# mmu6100cp.net
KiCad netlist of a schematic drawn in EAGLE
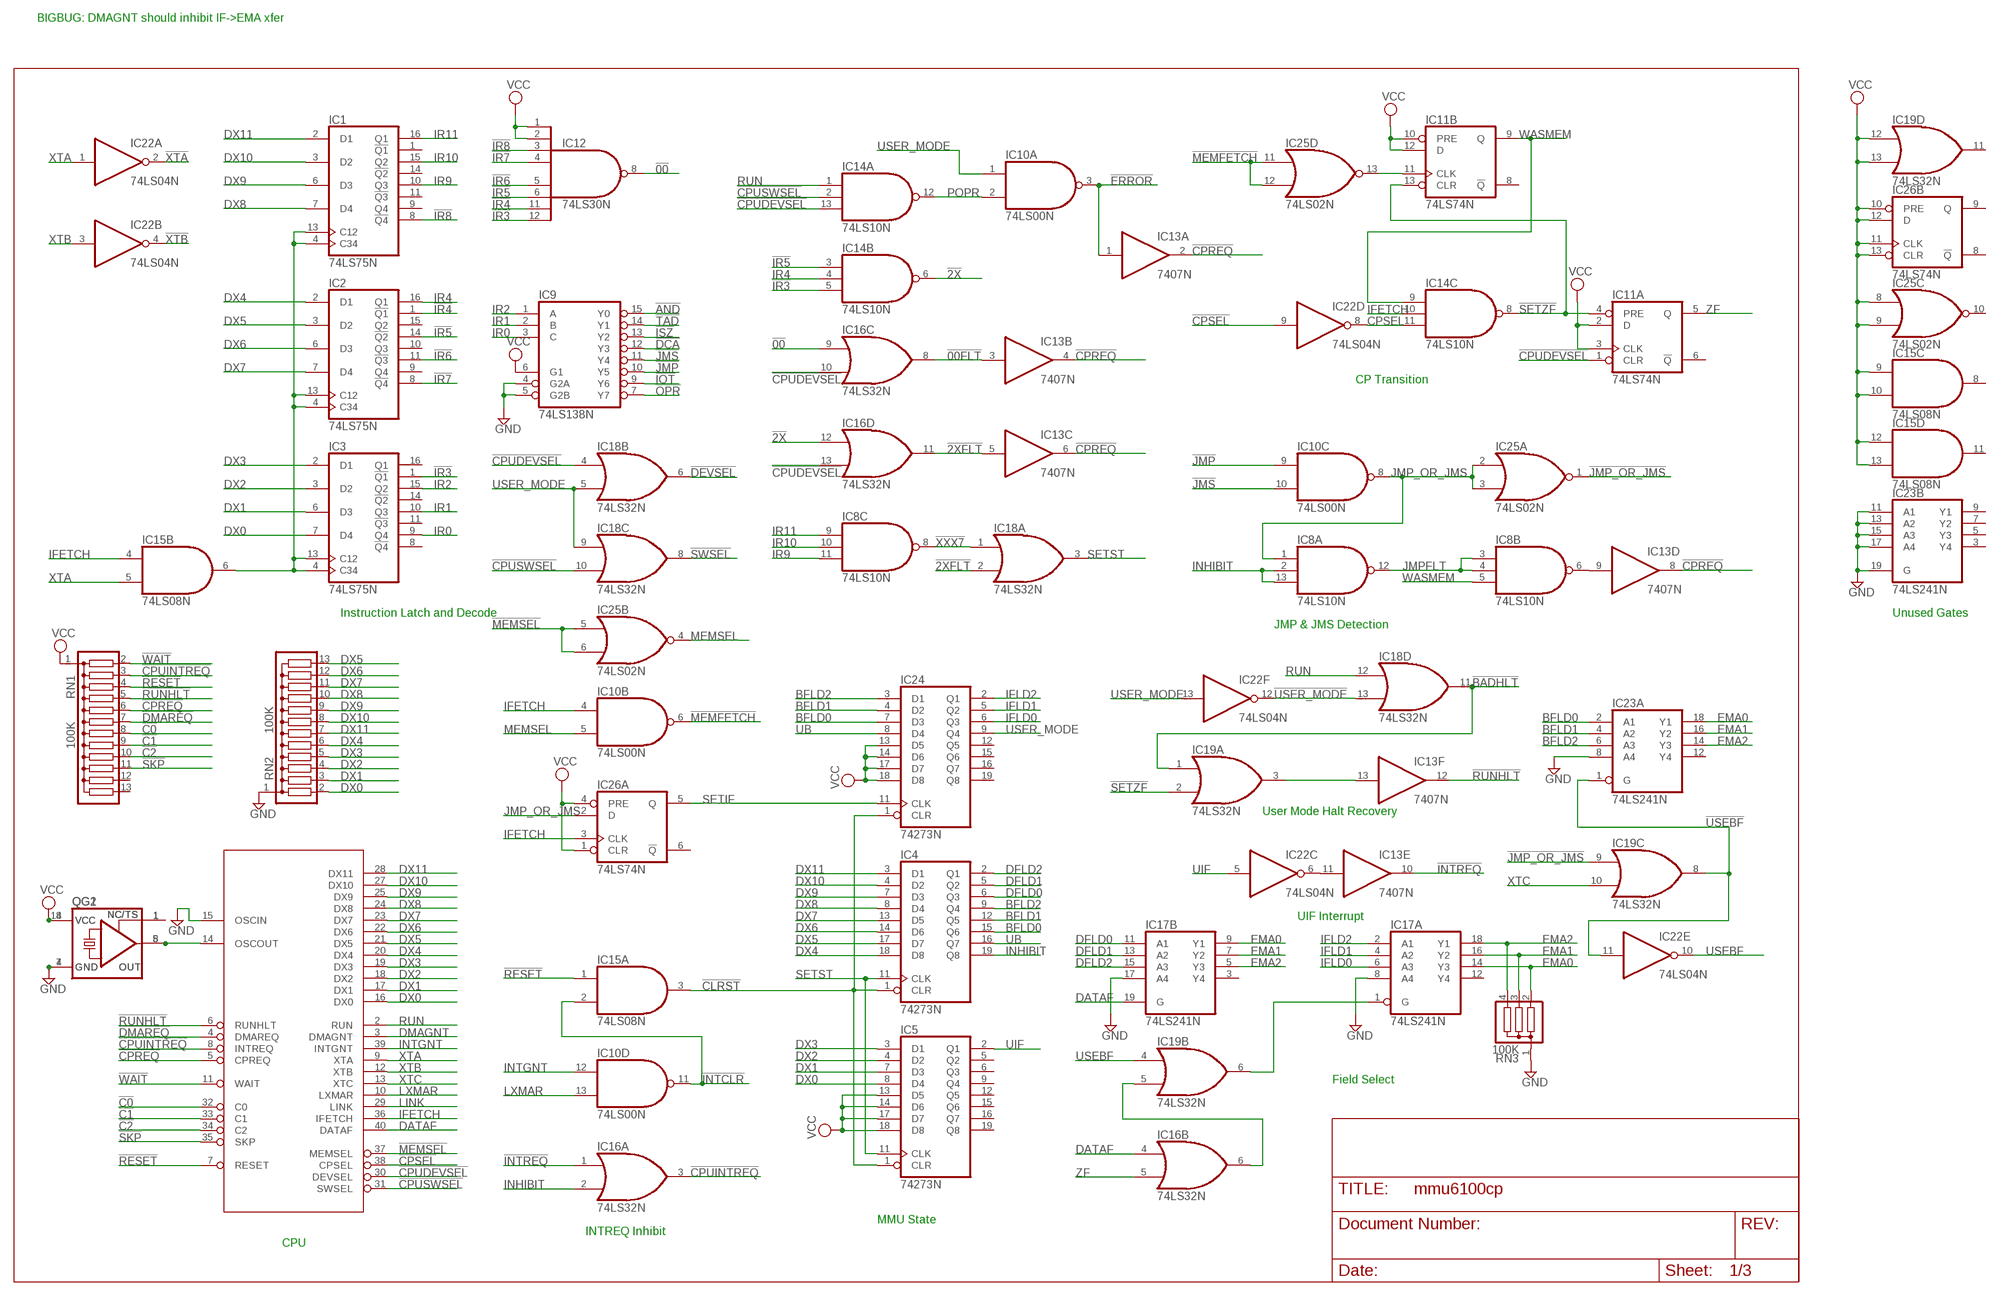
[diagram p0: schematic, sheet 1]
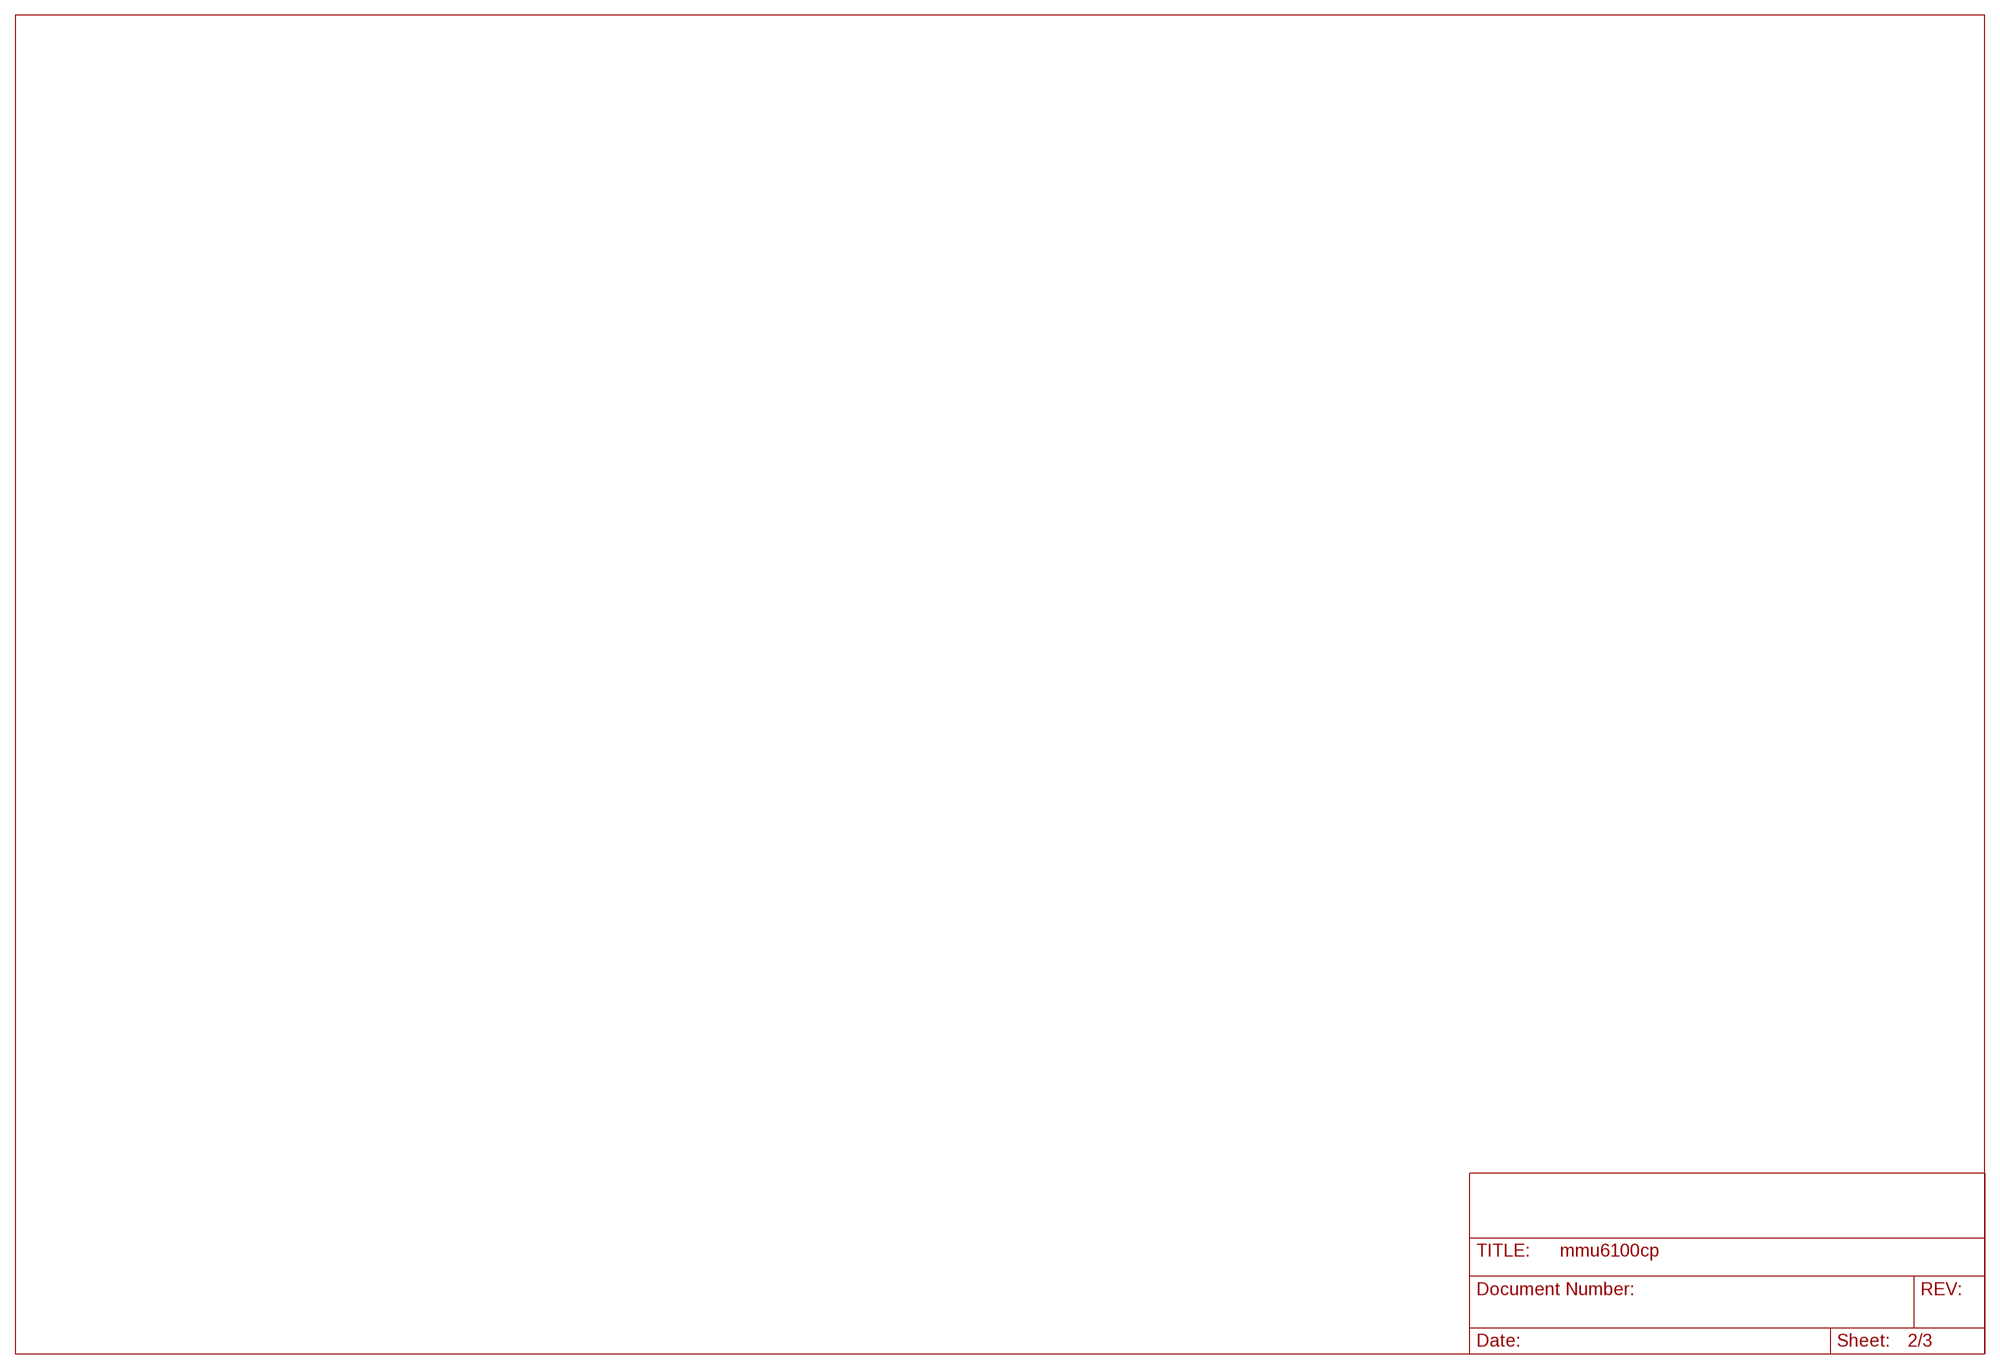
[diagram p1: schematic, sheet 2]
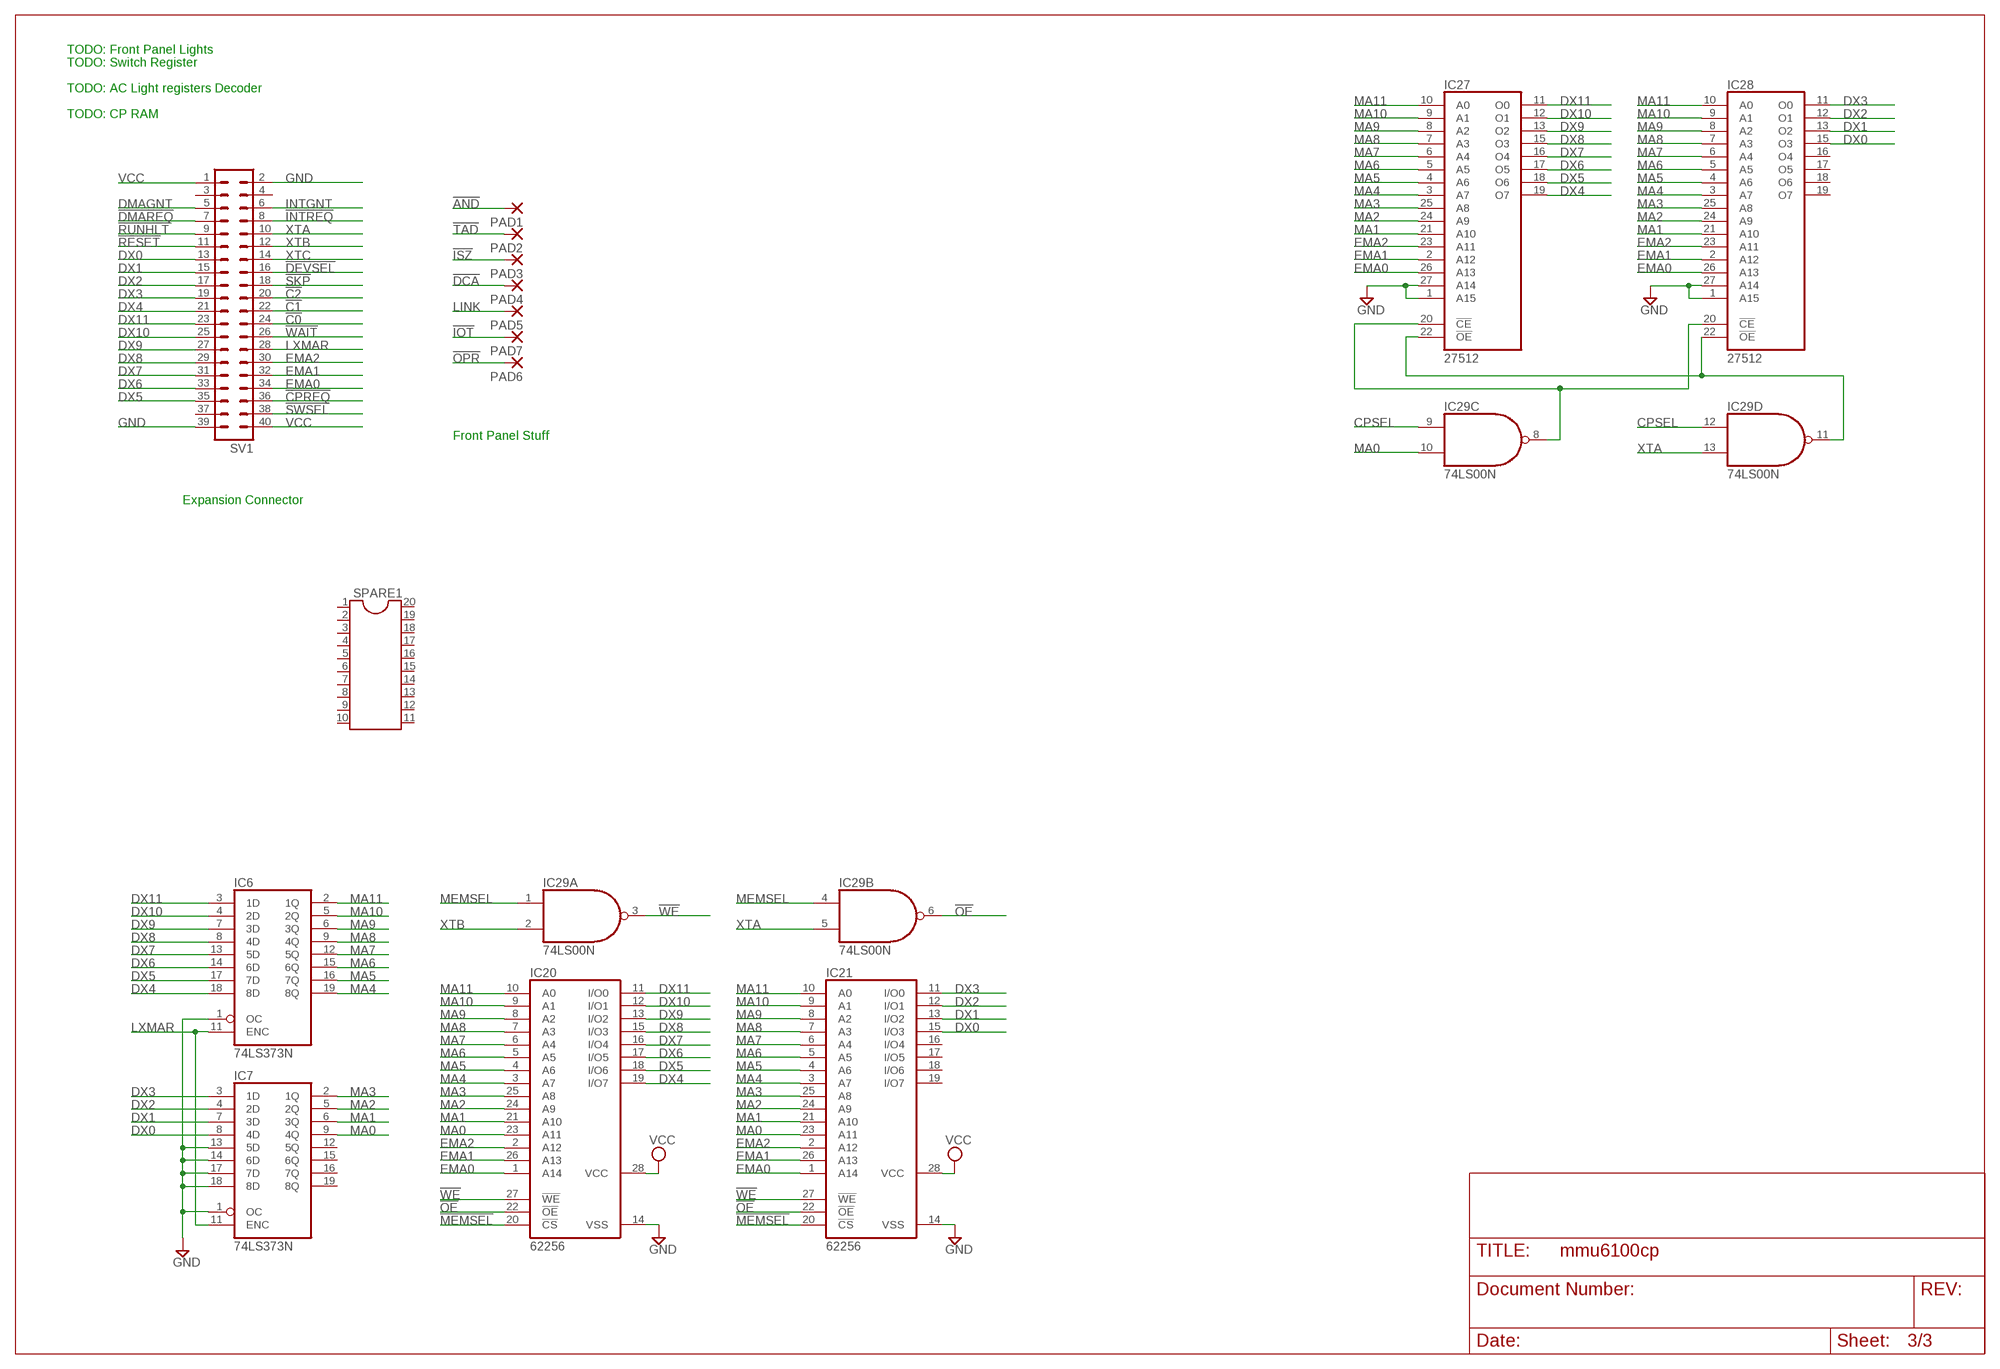
[diagram p2: schematic, sheet 3]

(export (version "E")
  (design (tool "Eeschema 10.0.6"))
  (components
    (comp (ref "IC6")
      (value "74LS373N")
      (footprint "eagle-import:DIL20")
      (libsource (lib "eagle-import") (part "74373NLS"))
    )
    (comp (ref "IC7")
      (value "74LS373N")
      (footprint "eagle-import:DIL20")
      (libsource (lib "eagle-import") (part "74373NLS"))
    )
    (comp (ref "IC20")
      (value "62256")
      (footprint "eagle-import:DIL28-6")
      (libsource (lib "eagle-import") (part "62256P"))
    )
    (comp (ref "IC21")
      (value "62256")
      (footprint "eagle-import:DIL28-6")
      (libsource (lib "eagle-import") (part "62256P"))
    )
    (comp (ref "IC27")
      (value "27512")
      (footprint "eagle-import:DIL28")
      (libsource (lib "eagle-import") (part "27512"))
    )
    (comp (ref "IC28")
      (value "27512")
      (footprint "eagle-import:DIL28")
      (libsource (lib "eagle-import") (part "27512"))
    )
    (comp (ref "IC29")
      (value "74LS00N")
      (footprint "eagle-import:DIL14")
      (libsource (lib "eagle-import") (part "7400NLS"))
    )
    (comp (ref "PAD1")
      (value "2,15/1,0")
      (footprint "eagle-import:2,15_1,0")
      (libsource (lib "eagle-import") (part "2,15/1,0"))
    )
    (comp (ref "PAD2")
      (value "2,15/1,0")
      (footprint "eagle-import:2,15_1,0")
      (libsource (lib "eagle-import") (part "2,15/1,0"))
    )
    (comp (ref "PAD3")
      (value "2,15/1,0")
      (footprint "eagle-import:2,15_1,0")
      (libsource (lib "eagle-import") (part "2,15/1,0"))
    )
    (comp (ref "PAD4")
      (value "2,15/1,0")
      (footprint "eagle-import:2,15_1,0")
      (libsource (lib "eagle-import") (part "2,15/1,0"))
    )
    (comp (ref "PAD5")
      (value "2,15/1,0")
      (footprint "eagle-import:2,15_1,0")
      (libsource (lib "eagle-import") (part "2,15/1,0"))
    )
    (comp (ref "PAD6")
      (value "2,15/1,0")
      (footprint "eagle-import:2,15_1,0")
      (libsource (lib "eagle-import") (part "2,15/1,0"))
    )
    (comp (ref "PAD7")
      (value "2,15/1,0")
      (footprint "eagle-import:2,15_1,0")
      (libsource (lib "eagle-import") (part "2,15/1,0"))
    )
    (comp (ref "SPARE1")
      (value "DIL20")
      (footprint "eagle-import:DIL20")
      (libsource (lib "eagle-import") (part "DIL20"))
    )
    (comp (ref "SV1")
      (value "MA20-2")
      (footprint "eagle-import:MA20-2")
      (libsource (lib "eagle-import") (part "MA20-2"))
    )
    (comp (ref "CPU")
      (value "IM6100")
      (footprint "eagle-import:DIL40")
      (libsource (lib "eagle-import") (part "IM6100"))
    )
    (comp (ref "IC1")
      (value "74LS75N")
      (footprint "eagle-import:DIL16")
      (libsource (lib "eagle-import") (part "7475NLS"))
    )
    (comp (ref "IC2")
      (value "74LS75N")
      (footprint "eagle-import:DIL16")
      (libsource (lib "eagle-import") (part "7475NLS"))
    )
    (comp (ref "IC3")
      (value "74LS75N")
      (footprint "eagle-import:DIL16")
      (libsource (lib "eagle-import") (part "7475NLS"))
    )
    (comp (ref "IC4")
      (value "74273N")
      (footprint "eagle-import:DIL20")
      (libsource (lib "eagle-import") (part "74273N"))
    )
    (comp (ref "IC5")
      (value "74273N")
      (footprint "eagle-import:DIL20")
      (libsource (lib "eagle-import") (part "74273N"))
    )
    (comp (ref "IC8")
      (value "74LS10N")
      (footprint "eagle-import:DIL14")
      (libsource (lib "eagle-import") (part "7410NLS"))
    )
    (comp (ref "IC9")
      (value "74LS138N")
      (footprint "eagle-import:DIL16")
      (libsource (lib "eagle-import") (part "74138NLS"))
    )
    (comp (ref "IC10")
      (value "74LS00N")
      (footprint "eagle-import:DIL14")
      (libsource (lib "eagle-import") (part "7400NLS"))
    )
    (comp (ref "IC11")
      (value "74LS74N")
      (footprint "eagle-import:DIL14")
      (libsource (lib "eagle-import") (part "7474NLS"))
    )
    (comp (ref "IC12")
      (value "74LS30N")
      (footprint "eagle-import:DIL14")
      (libsource (lib "eagle-import") (part "7430NLS"))
    )
    (comp (ref "IC13")
      (value "7407N")
      (footprint "eagle-import:DIL14")
      (libsource (lib "eagle-import") (part "7407N"))
    )
    (comp (ref "IC14")
      (value "74LS10N")
      (footprint "eagle-import:DIL14")
      (libsource (lib "eagle-import") (part "7410NLS"))
    )
    (comp (ref "IC15")
      (value "74LS08N")
      (footprint "eagle-import:DIL14")
      (libsource (lib "eagle-import") (part "7408NLS"))
    )
    (comp (ref "IC16")
      (value "74LS32N")
      (footprint "eagle-import:DIL14")
      (libsource (lib "eagle-import") (part "7432NLS"))
    )
    (comp (ref "IC17")
      (value "74LS241N")
      (footprint "eagle-import:DIL20")
      (libsource (lib "eagle-import") (part "74241NLS"))
    )
    (comp (ref "IC18")
      (value "74LS32N")
      (footprint "eagle-import:DIL14")
      (libsource (lib "eagle-import") (part "7432NLS"))
    )
    (comp (ref "IC19")
      (value "74LS32N")
      (footprint "eagle-import:DIL14")
      (libsource (lib "eagle-import") (part "7432NLS"))
    )
    (comp (ref "IC22")
      (value "74LS04N")
      (footprint "eagle-import:DIL14")
      (libsource (lib "eagle-import") (part "7404NLS"))
    )
    (comp (ref "IC23")
      (value "74LS241N")
      (footprint "eagle-import:DIL20")
      (libsource (lib "eagle-import") (part "74241NLS"))
    )
    (comp (ref "IC24")
      (value "74273N")
      (footprint "eagle-import:DIL20")
      (libsource (lib "eagle-import") (part "74273N"))
    )
    (comp (ref "IC25")
      (value "74LS02N")
      (footprint "eagle-import:DIL14")
      (libsource (lib "eagle-import") (part "7402NLS"))
    )
    (comp (ref "IC26")
      (value "74LS74N")
      (footprint "eagle-import:DIL14")
      (libsource (lib "eagle-import") (part "7474NLS"))
    )
    (comp (ref "QG1")
      (value "XO-8")
      (footprint "eagle-import:DIL08S")
      (libsource (lib "eagle-import") (part "XO-8"))
    )
    (comp (ref "QG2")
      (value "XO-14")
      (footprint "eagle-import:DIL14S")
      (libsource (lib "eagle-import") (part "XO-14"))
    )
    (comp (ref "RN1")
      (value "100K")
      (footprint "eagle-import:SIL13")
      (libsource (lib "eagle-import") (part "G12R"))
    )
    (comp (ref "RN2")
      (value "100K")
      (footprint "eagle-import:SIL13")
      (libsource (lib "eagle-import") (part "G12R"))
    )
    (comp (ref "RN3")
      (value "100K")
      (footprint "eagle-import:SIL4")
      (libsource (lib "eagle-import") (part "G03R"))
    )
  )
  (nets
    (net (code "1") (name "BFLD0") (class "Default")
      (node (ref "IC23") (pin "2") (pinfunction "A1_2") (pintype "input"))
      (node (ref "IC24") (pin "7") (pinfunction "D3_7") (pintype "input"))
      (node (ref "IC4") (pin "15") (pinfunction "Q6_15") (pintype "output"))
    )
    (net (code "2") (name "BFLD1") (class "Default")
      (node (ref "IC23") (pin "4") (pinfunction "A2_4") (pintype "input"))
      (node (ref "IC24") (pin "4") (pinfunction "D2_4") (pintype "input"))
      (node (ref "IC4") (pin "12") (pinfunction "Q5_12") (pintype "output"))
    )
    (net (code "3") (name "BFLD2") (class "Default")
      (node (ref "IC23") (pin "6") (pinfunction "A3_6") (pintype "input"))
      (node (ref "IC24") (pin "3") (pinfunction "D1_3") (pintype "input"))
      (node (ref "IC4") (pin "9") (pinfunction "Q4_9") (pintype "output"))
    )
    (net (code "4") (name "CPSEL") (class "Default")
      (node (ref "IC14") (pin "11") (pinfunction "I2_11") (pintype "input"))
      (node (ref "IC22") (pin "8") (pinfunction "O_8") (pintype "output"))
      (node (ref "IC29") (pin "12") (pinfunction "I0_12") (pintype "input"))
      (node (ref "IC29") (pin "9") (pinfunction "I0_9") (pintype "input"))
    )
    (net (code "5") (name "DATAF") (class "Default")
      (node (ref "CPU") (pin "40") (pinfunction "DATAF_40") (pintype "output"))
      (node (ref "IC16") (pin "4") (pinfunction "I0_4") (pintype "input"))
      (node (ref "IC17") (pin "19") (pinfunction "G_19") (pintype "input"))
    )
    (net (code "6") (name "DFLD0") (class "Default")
      (node (ref "IC17") (pin "11") (pinfunction "A1_11") (pintype "input"))
      (node (ref "IC4") (pin "6") (pinfunction "Q3_6") (pintype "output"))
    )
    (net (code "7") (name "DFLD1") (class "Default")
      (node (ref "IC17") (pin "13") (pinfunction "A2_13") (pintype "input"))
      (node (ref "IC4") (pin "5") (pinfunction "Q2_5") (pintype "output"))
    )
    (net (code "8") (name "DFLD2") (class "Default")
      (node (ref "IC17") (pin "15") (pinfunction "A3_15") (pintype "input"))
      (node (ref "IC4") (pin "2") (pinfunction "Q1_2") (pintype "output"))
    )
    (net (code "9") (name "DMAGNT") (class "Default")
      (node (ref "CPU") (pin "3") (pinfunction "DMAGNT_3") (pintype "output"))
      (node (ref "SV1") (pin "5") (pinfunction "5_5") (pintype "passive"))
    )
    (net (code "10") (name "DX0") (class "Default")
      (node (ref "CPU") (pin "16") (pinfunction "DX0_16") (pintype "bidirectional"))
      (node (ref "IC21") (pin "15") (pinfunction "I/O3_15") (pintype "bidirectional"))
      (node (ref "IC28") (pin "15") (pinfunction "O3_15") (pintype "tri_state"))
      (node (ref "IC3") (pin "7") (pinfunction "D4_7") (pintype "input"))
      (node (ref "IC5") (pin "8") (pinfunction "D4_8") (pintype "input"))
      (node (ref "IC7") (pin "8") (pinfunction "4D_8") (pintype "input"))
      (node (ref "RN2") (pin "2") (pinfunction "2_2") (pintype "passive"))
      (node (ref "SV1") (pin "13") (pinfunction "13_13") (pintype "passive"))
    )
    (net (code "11") (name "DX1") (class "Default")
      (node (ref "CPU") (pin "17") (pinfunction "DX1_17") (pintype "bidirectional"))
      (node (ref "IC21") (pin "13") (pinfunction "I/O2_13") (pintype "bidirectional"))
      (node (ref "IC28") (pin "13") (pinfunction "O2_13") (pintype "tri_state"))
      (node (ref "IC3") (pin "6") (pinfunction "D3_6") (pintype "input"))
      (node (ref "IC5") (pin "7") (pinfunction "D3_7") (pintype "input"))
      (node (ref "IC7") (pin "7") (pinfunction "3D_7") (pintype "input"))
      (node (ref "RN2") (pin "3") (pinfunction "3_3") (pintype "passive"))
      (node (ref "SV1") (pin "15") (pinfunction "15_15") (pintype "passive"))
    )
    (net (code "12") (name "DX2") (class "Default")
      (node (ref "CPU") (pin "18") (pinfunction "DX2_18") (pintype "bidirectional"))
      (node (ref "IC21") (pin "12") (pinfunction "I/O1_12") (pintype "bidirectional"))
      (node (ref "IC28") (pin "12") (pinfunction "O1_12") (pintype "tri_state"))
      (node (ref "IC3") (pin "3") (pinfunction "D2_3") (pintype "input"))
      (node (ref "IC5") (pin "4") (pinfunction "D2_4") (pintype "input"))
      (node (ref "IC7") (pin "4") (pinfunction "2D_4") (pintype "input"))
      (node (ref "RN2") (pin "4") (pinfunction "4_4") (pintype "passive"))
      (node (ref "SV1") (pin "17") (pinfunction "17_17") (pintype "passive"))
    )
    (net (code "13") (name "DX3") (class "Default")
      (node (ref "CPU") (pin "19") (pinfunction "DX3_19") (pintype "bidirectional"))
      (node (ref "IC21") (pin "11") (pinfunction "I/O0_11") (pintype "bidirectional"))
      (node (ref "IC28") (pin "11") (pinfunction "O0_11") (pintype "tri_state"))
      (node (ref "IC3") (pin "2") (pinfunction "D1_2") (pintype "input"))
      (node (ref "IC5") (pin "3") (pinfunction "D1_3") (pintype "input"))
      (node (ref "IC7") (pin "3") (pinfunction "1D_3") (pintype "input"))
      (node (ref "RN2") (pin "5") (pinfunction "5_5") (pintype "passive"))
      (node (ref "SV1") (pin "19") (pinfunction "19_19") (pintype "passive"))
    )
    (net (code "14") (name "DX4") (class "Default")
      (node (ref "CPU") (pin "20") (pinfunction "DX4_20") (pintype "bidirectional"))
      (node (ref "IC2") (pin "2") (pinfunction "D1_2") (pintype "input"))
      (node (ref "IC20") (pin "19") (pinfunction "I/O7_19") (pintype "bidirectional"))
      (node (ref "IC27") (pin "19") (pinfunction "O7_19") (pintype "tri_state"))
      (node (ref "IC4") (pin "18") (pinfunction "D8_18") (pintype "input"))
      (node (ref "IC6") (pin "18") (pinfunction "8D_18") (pintype "input"))
      (node (ref "RN2") (pin "6") (pinfunction "6_6") (pintype "passive"))
      (node (ref "SV1") (pin "21") (pinfunction "21_21") (pintype "passive"))
    )
    (net (code "15") (name "DX5") (class "Default")
      (node (ref "CPU") (pin "21") (pinfunction "DX5_21") (pintype "bidirectional"))
      (node (ref "IC2") (pin "3") (pinfunction "D2_3") (pintype "input"))
      (node (ref "IC20") (pin "18") (pinfunction "I/O6_18") (pintype "bidirectional"))
      (node (ref "IC27") (pin "18") (pinfunction "O6_18") (pintype "tri_state"))
      (node (ref "IC4") (pin "17") (pinfunction "D7_17") (pintype "input"))
      (node (ref "IC6") (pin "17") (pinfunction "7D_17") (pintype "input"))
      (node (ref "RN2") (pin "13") (pinfunction "13_13") (pintype "passive"))
      (node (ref "SV1") (pin "35") (pinfunction "35_35") (pintype "passive"))
    )
    (net (code "16") (name "DX6") (class "Default")
      (node (ref "CPU") (pin "22") (pinfunction "DX6_22") (pintype "bidirectional"))
      (node (ref "IC2") (pin "6") (pinfunction "D3_6") (pintype "input"))
      (node (ref "IC20") (pin "17") (pinfunction "I/O5_17") (pintype "bidirectional"))
      (node (ref "IC27") (pin "17") (pinfunction "O5_17") (pintype "tri_state"))
      (node (ref "IC4") (pin "14") (pinfunction "D6_14") (pintype "input"))
      (node (ref "IC6") (pin "14") (pinfunction "6D_14") (pintype "input"))
      (node (ref "RN2") (pin "12") (pinfunction "12_12") (pintype "passive"))
      (node (ref "SV1") (pin "33") (pinfunction "33_33") (pintype "passive"))
    )
    (net (code "17") (name "DX7") (class "Default")
      (node (ref "CPU") (pin "23") (pinfunction "DX7_23") (pintype "bidirectional"))
      (node (ref "IC2") (pin "7") (pinfunction "D4_7") (pintype "input"))
      (node (ref "IC20") (pin "16") (pinfunction "I/O4_16") (pintype "bidirectional"))
      (node (ref "IC27") (pin "16") (pinfunction "O4_16") (pintype "tri_state"))
      (node (ref "IC4") (pin "13") (pinfunction "D5_13") (pintype "input"))
      (node (ref "IC6") (pin "13") (pinfunction "5D_13") (pintype "input"))
      (node (ref "RN2") (pin "11") (pinfunction "11_11") (pintype "passive"))
      (node (ref "SV1") (pin "31") (pinfunction "31_31") (pintype "passive"))
    )
    (net (code "18") (name "DX8") (class "Default")
      (node (ref "CPU") (pin "24") (pinfunction "DX8_24") (pintype "bidirectional"))
      (node (ref "IC1") (pin "7") (pinfunction "D4_7") (pintype "input"))
      (node (ref "IC20") (pin "15") (pinfunction "I/O3_15") (pintype "bidirectional"))
      (node (ref "IC27") (pin "15") (pinfunction "O3_15") (pintype "tri_state"))
      (node (ref "IC4") (pin "8") (pinfunction "D4_8") (pintype "input"))
      (node (ref "IC6") (pin "8") (pinfunction "4D_8") (pintype "input"))
      (node (ref "RN2") (pin "10") (pinfunction "10_10") (pintype "passive"))
      (node (ref "SV1") (pin "29") (pinfunction "29_29") (pintype "passive"))
    )
    (net (code "19") (name "DX9") (class "Default")
      (node (ref "CPU") (pin "25") (pinfunction "DX9_25") (pintype "bidirectional"))
      (node (ref "IC1") (pin "6") (pinfunction "D3_6") (pintype "input"))
      (node (ref "IC20") (pin "13") (pinfunction "I/O2_13") (pintype "bidirectional"))
      (node (ref "IC27") (pin "13") (pinfunction "O2_13") (pintype "tri_state"))
      (node (ref "IC4") (pin "7") (pinfunction "D3_7") (pintype "input"))
      (node (ref "IC6") (pin "7") (pinfunction "3D_7") (pintype "input"))
      (node (ref "RN2") (pin "9") (pinfunction "9_9") (pintype "passive"))
      (node (ref "SV1") (pin "27") (pinfunction "27_27") (pintype "passive"))
    )
    (net (code "20") (name "DX10") (class "Default")
      (node (ref "CPU") (pin "27") (pinfunction "DX10_27") (pintype "bidirectional"))
      (node (ref "IC1") (pin "3") (pinfunction "D2_3") (pintype "input"))
      (node (ref "IC20") (pin "12") (pinfunction "I/O1_12") (pintype "bidirectional"))
      (node (ref "IC27") (pin "12") (pinfunction "O1_12") (pintype "tri_state"))
      (node (ref "IC4") (pin "4") (pinfunction "D2_4") (pintype "input"))
      (node (ref "IC6") (pin "4") (pinfunction "2D_4") (pintype "input"))
      (node (ref "RN2") (pin "8") (pinfunction "8_8") (pintype "passive"))
      (node (ref "SV1") (pin "25") (pinfunction "25_25") (pintype "passive"))
    )
    (net (code "21") (name "DX11") (class "Default")
      (node (ref "CPU") (pin "28") (pinfunction "DX11_28") (pintype "bidirectional"))
      (node (ref "IC1") (pin "2") (pinfunction "D1_2") (pintype "input"))
      (node (ref "IC20") (pin "11") (pinfunction "I/O0_11") (pintype "bidirectional"))
      (node (ref "IC27") (pin "11") (pinfunction "O0_11") (pintype "tri_state"))
      (node (ref "IC4") (pin "3") (pinfunction "D1_3") (pintype "input"))
      (node (ref "IC6") (pin "3") (pinfunction "1D_3") (pintype "input"))
      (node (ref "RN2") (pin "7") (pinfunction "7_7") (pintype "passive"))
      (node (ref "SV1") (pin "23") (pinfunction "23_23") (pintype "passive"))
    )
    (net (code "22") (name "EMA0") (class "Default")
      (node (ref "IC17") (pin "14") (pinfunction "Y3_14") (pintype "tri_state"))
      (node (ref "IC17") (pin "9") (pinfunction "Y1_9") (pintype "tri_state"))
      (node (ref "IC20") (pin "1") (pinfunction "A14_1") (pintype "input"))
      (node (ref "IC21") (pin "1") (pinfunction "A14_1") (pintype "input"))
      (node (ref "IC23") (pin "18") (pinfunction "Y1_18") (pintype "tri_state"))
      (node (ref "IC27") (pin "26") (pinfunction "A13_26") (pintype "input"))
      (node (ref "IC28") (pin "26") (pinfunction "A13_26") (pintype "input"))
      (node (ref "RN3") (pin "2") (pinfunction "2_2") (pintype "passive"))
      (node (ref "SV1") (pin "34") (pinfunction "34_34") (pintype "passive"))
    )
    (net (code "23") (name "EMA1") (class "Default")
      (node (ref "IC17") (pin "16") (pinfunction "Y2_16") (pintype "tri_state"))
      (node (ref "IC17") (pin "7") (pinfunction "Y2_7") (pintype "tri_state"))
      (node (ref "IC20") (pin "26") (pinfunction "A13_26") (pintype "input"))
      (node (ref "IC21") (pin "26") (pinfunction "A13_26") (pintype "input"))
      (node (ref "IC23") (pin "16") (pinfunction "Y2_16") (pintype "tri_state"))
      (node (ref "IC27") (pin "2") (pinfunction "A12_2") (pintype "input"))
      (node (ref "IC28") (pin "2") (pinfunction "A12_2") (pintype "input"))
      (node (ref "RN3") (pin "3") (pinfunction "3_3") (pintype "passive"))
      (node (ref "SV1") (pin "32") (pinfunction "32_32") (pintype "passive"))
    )
    (net (code "24") (name "EMA2") (class "Default")
      (node (ref "IC17") (pin "18") (pinfunction "Y1_18") (pintype "tri_state"))
      (node (ref "IC17") (pin "5") (pinfunction "Y3_5") (pintype "tri_state"))
      (node (ref "IC20") (pin "2") (pinfunction "A12_2") (pintype "input"))
      (node (ref "IC21") (pin "2") (pinfunction "A12_2") (pintype "input"))
      (node (ref "IC23") (pin "14") (pinfunction "Y3_14") (pintype "tri_state"))
      (node (ref "IC27") (pin "23") (pinfunction "A11_23") (pintype "input"))
      (node (ref "IC28") (pin "23") (pinfunction "A11_23") (pintype "input"))
      (node (ref "RN3") (pin "4") (pinfunction "4_4") (pintype "passive"))
      (node (ref "SV1") (pin "30") (pinfunction "30_30") (pintype "passive"))
    )
    (net (code "25") (name "GND") (class "Default")
      (node (ref "CPU") (pin "15") (pinfunction "OSCIN_15") (pintype "input"))
      (node (ref "IC17") (pin "17") (pinfunction "A4_17") (pintype "input"))
      (node (ref "IC17") (pin "8") (pinfunction "A4_8") (pintype "input"))
      (node (ref "IC20") (pin "14") (pinfunction "VSS_14") (pintype "power_in"))
      (node (ref "IC21") (pin "14") (pinfunction "VSS_14") (pintype "power_in"))
      (node (ref "IC23") (pin "11") (pinfunction "A1_11") (pintype "input"))
      (node (ref "IC23") (pin "13") (pinfunction "A2_13") (pintype "input"))
      (node (ref "IC23") (pin "15") (pinfunction "A3_15") (pintype "input"))
      (node (ref "IC23") (pin "17") (pinfunction "A4_17") (pintype "input"))
      (node (ref "IC23") (pin "19") (pinfunction "G_19") (pintype "input"))
      (node (ref "IC23") (pin "8") (pinfunction "A4_8") (pintype "input"))
      (node (ref "IC27") (pin "1") (pinfunction "A15_1") (pintype "input"))
      (node (ref "IC27") (pin "27") (pinfunction "A14_27") (pintype "input"))
      (node (ref "IC28") (pin "1") (pinfunction "A15_1") (pintype "input"))
      (node (ref "IC28") (pin "27") (pinfunction "A14_27") (pintype "input"))
      (node (ref "IC6") (pin "1") (pinfunction "OC_1") (pintype "input"))
      (node (ref "IC7") (pin "1") (pinfunction "OC_1") (pintype "input"))
      (node (ref "IC7") (pin "13") (pinfunction "5D_13") (pintype "input"))
      (node (ref "IC7") (pin "14") (pinfunction "6D_14") (pintype "input"))
      (node (ref "IC7") (pin "17") (pinfunction "7D_17") (pintype "input"))
      (node (ref "IC7") (pin "18") (pinfunction "8D_18") (pintype "input"))
      (node (ref "IC9") (pin "4") (pinfunction "G2A_4") (pintype "input"))
      (node (ref "IC9") (pin "5") (pinfunction "G2B_5") (pintype "input"))
      (node (ref "QG1") (pin "4") (pinfunction "GND_4") (pintype "power_in"))
      (node (ref "QG2") (pin "7") (pinfunction "GND_7") (pintype "power_in"))
      (node (ref "RN2") (pin "1") (pinfunction "1_1") (pintype "passive"))
      (node (ref "RN3") (pin "1") (pinfunction "1_1") (pintype "passive"))
      (node (ref "SV1") (pin "2") (pinfunction "2_2") (pintype "passive"))
      (node (ref "SV1") (pin "39") (pinfunction "39_39") (pintype "passive"))
    )
    (net (code "26") (name "IFETCH") (class "Default")
      (node (ref "CPU") (pin "36") (pinfunction "IFETCH_36") (pintype "output"))
      (node (ref "IC10") (pin "4") (pinfunction "I0_4") (pintype "input"))
      (node (ref "IC14") (pin "10") (pinfunction "I1_10") (pintype "input"))
      (node (ref "IC15") (pin "4") (pinfunction "I0_4") (pintype "input"))
      (node (ref "IC26") (pin "3") (pinfunction "CLK_3") (pintype "input"))
    )
    (net (code "27") (name "IFLD0") (class "Default")
      (node (ref "IC17") (pin "6") (pinfunction "A3_6") (pintype "input"))
      (node (ref "IC24") (pin "6") (pinfunction "Q3_6") (pintype "output"))
    )
    (net (code "28") (name "IFLD1") (class "Default")
      (node (ref "IC17") (pin "4") (pinfunction "A2_4") (pintype "input"))
      (node (ref "IC24") (pin "5") (pinfunction "Q2_5") (pintype "output"))
    )
    (net (code "29") (name "IFLD2") (class "Default")
      (node (ref "IC17") (pin "2") (pinfunction "A1_2") (pintype "input"))
      (node (ref "IC24") (pin "2") (pinfunction "Q1_2") (pintype "output"))
    )
    (net (code "30") (name "INHIBIT") (class "Default")
      (node (ref "IC16") (pin "2") (pinfunction "I1_2") (pintype "input"))
      (node (ref "IC4") (pin "19") (pinfunction "Q8_19") (pintype "output"))
      (node (ref "IC8") (pin "13") (pinfunction "I2_13") (pintype "input"))
      (node (ref "IC8") (pin "2") (pinfunction "I1_2") (pintype "input"))
    )
    (net (code "31") (name "INTGNT") (class "Default")
      (node (ref "CPU") (pin "39") (pinfunction "INTGNT_39") (pintype "output"))
      (node (ref "IC10") (pin "12") (pinfunction "I0_12") (pintype "input"))
      (node (ref "SV1") (pin "6") (pinfunction "6_6") (pintype "passive"))
    )
    (net (code "32") (name "IR0") (class "Default")
      (node (ref "IC3") (pin "9") (pinfunction "Q4_9") (pintype "output"))
      (node (ref "IC9") (pin "3") (pinfunction "C_3") (pintype "input"))
    )
    (net (code "33") (name "IR1") (class "Default")
      (node (ref "IC3") (pin "10") (pinfunction "Q3_10") (pintype "output"))
      (node (ref "IC9") (pin "2") (pinfunction "B_2") (pintype "input"))
    )
    (net (code "34") (name "IR2") (class "Default")
      (node (ref "IC3") (pin "15") (pinfunction "Q2_15") (pintype "output"))
      (node (ref "IC9") (pin "1") (pinfunction "A_1") (pintype "input"))
    )
    (net (code "35") (name "IR4") (class "Default")
      (node (ref "IC14") (pin "4") (pinfunction "I1_4") (pintype "input"))
      (node (ref "IC2") (pin "16") (pinfunction "Q1_16") (pintype "output"))
    )
    (net (code "36") (name "IR9") (class "Default")
      (node (ref "IC1") (pin "10") (pinfunction "Q3_10") (pintype "output"))
      (node (ref "IC8") (pin "11") (pinfunction "I2_11") (pintype "input"))
    )
    (net (code "37") (name "IR10") (class "Default")
      (node (ref "IC1") (pin "15") (pinfunction "Q2_15") (pintype "output"))
      (node (ref "IC8") (pin "10") (pinfunction "I1_10") (pintype "input"))
    )
    (net (code "38") (name "IR11") (class "Default")
      (node (ref "IC1") (pin "16") (pinfunction "Q1_16") (pintype "output"))
      (node (ref "IC8") (pin "9") (pinfunction "I0_9") (pintype "input"))
    )
    (net (code "39") (name "JMPFLT") (class "Default")
      (node (ref "IC8") (pin "12") (pinfunction "O_12") (pintype "output"))
      (node (ref "IC8") (pin "3") (pinfunction "I0_3") (pintype "input"))
      (node (ref "IC8") (pin "4") (pinfunction "I1_4") (pintype "input"))
    )
    (net (code "40") (name "JMP_OR_JMS") (class "Default")
      (node (ref "IC10") (pin "8") (pinfunction "O_8") (pintype "output"))
      (node (ref "IC25") (pin "2") (pinfunction "I0_2") (pintype "input"))
      (node (ref "IC25") (pin "3") (pinfunction "I1_3") (pintype "input"))
      (node (ref "IC26") (pin "2") (pinfunction "D_2") (pintype "input"))
      (node (ref "IC8") (pin "1") (pinfunction "I0_1") (pintype "input"))
    )
    (net (code "41") (name "LINK") (class "Default")
      (node (ref "CPU") (pin "29") (pinfunction "LINK_29") (pintype "output"))
      (node (ref "PAD5") (pin "1") (pinfunction "P_1") (pintype "passive"))
    )
    (net (code "42") (name "LXMAR") (class "Default")
      (node (ref "CPU") (pin "10") (pinfunction "LXMAR_10") (pintype "output"))
      (node (ref "IC10") (pin "13") (pinfunction "I1_13") (pintype "input"))
      (node (ref "IC6") (pin "11") (pinfunction "ENC_11") (pintype "input"))
      (node (ref "IC7") (pin "11") (pinfunction "ENC_11") (pintype "input"))
      (node (ref "SV1") (pin "28") (pinfunction "28_28") (pintype "passive"))
    )
    (net (code "43") (name "MA0") (class "Default")
      (node (ref "IC20") (pin "23") (pinfunction "A11_23") (pintype "input"))
      (node (ref "IC21") (pin "23") (pinfunction "A11_23") (pintype "input"))
      (node (ref "IC29") (pin "10") (pinfunction "I1_10") (pintype "input"))
      (node (ref "IC7") (pin "9") (pinfunction "4Q_9") (pintype "tri_state"))
    )
    (net (code "44") (name "MA1") (class "Default")
      (node (ref "IC20") (pin "21") (pinfunction "A10_21") (pintype "input"))
      (node (ref "IC21") (pin "21") (pinfunction "A10_21") (pintype "input"))
      (node (ref "IC27") (pin "21") (pinfunction "A10_21") (pintype "input"))
      (node (ref "IC28") (pin "21") (pinfunction "A10_21") (pintype "input"))
      (node (ref "IC7") (pin "6") (pinfunction "3Q_6") (pintype "tri_state"))
    )
    (net (code "45") (name "MA2") (class "Default")
      (node (ref "IC20") (pin "24") (pinfunction "A9_24") (pintype "input"))
      (node (ref "IC21") (pin "24") (pinfunction "A9_24") (pintype "input"))
      (node (ref "IC27") (pin "24") (pinfunction "A9_24") (pintype "input"))
      (node (ref "IC28") (pin "24") (pinfunction "A9_24") (pintype "input"))
      (node (ref "IC7") (pin "5") (pinfunction "2Q_5") (pintype "tri_state"))
    )
    (net (code "46") (name "MA3") (class "Default")
      (node (ref "IC20") (pin "25") (pinfunction "A8_25") (pintype "input"))
      (node (ref "IC21") (pin "25") (pinfunction "A8_25") (pintype "input"))
      (node (ref "IC27") (pin "25") (pinfunction "A8_25") (pintype "input"))
      (node (ref "IC28") (pin "25") (pinfunction "A8_25") (pintype "input"))
      (node (ref "IC7") (pin "2") (pinfunction "1Q_2") (pintype "tri_state"))
    )
    (net (code "47") (name "MA4") (class "Default")
      (node (ref "IC20") (pin "3") (pinfunction "A7_3") (pintype "input"))
      (node (ref "IC21") (pin "3") (pinfunction "A7_3") (pintype "input"))
      (node (ref "IC27") (pin "3") (pinfunction "A7_3") (pintype "input"))
      (node (ref "IC28") (pin "3") (pinfunction "A7_3") (pintype "input"))
      (node (ref "IC6") (pin "19") (pinfunction "8Q_19") (pintype "tri_state"))
    )
    (net (code "48") (name "MA5") (class "Default")
      (node (ref "IC20") (pin "4") (pinfunction "A6_4") (pintype "input"))
      (node (ref "IC21") (pin "4") (pinfunction "A6_4") (pintype "input"))
      (node (ref "IC27") (pin "4") (pinfunction "A6_4") (pintype "input"))
      (node (ref "IC28") (pin "4") (pinfunction "A6_4") (pintype "input"))
      (node (ref "IC6") (pin "16") (pinfunction "7Q_16") (pintype "tri_state"))
    )
    (net (code "49") (name "MA6") (class "Default")
      (node (ref "IC20") (pin "5") (pinfunction "A5_5") (pintype "input"))
      (node (ref "IC21") (pin "5") (pinfunction "A5_5") (pintype "input"))
      (node (ref "IC27") (pin "5") (pinfunction "A5_5") (pintype "input"))
      (node (ref "IC28") (pin "5") (pinfunction "A5_5") (pintype "input"))
      (node (ref "IC6") (pin "15") (pinfunction "6Q_15") (pintype "tri_state"))
    )
    (net (code "50") (name "MA7") (class "Default")
      (node (ref "IC20") (pin "6") (pinfunction "A4_6") (pintype "input"))
      (node (ref "IC21") (pin "6") (pinfunction "A4_6") (pintype "input"))
      (node (ref "IC27") (pin "6") (pinfunction "A4_6") (pintype "input"))
      (node (ref "IC28") (pin "6") (pinfunction "A4_6") (pintype "input"))
      (node (ref "IC6") (pin "12") (pinfunction "5Q_12") (pintype "tri_state"))
    )
    (net (code "51") (name "MA8") (class "Default")
      (node (ref "IC20") (pin "7") (pinfunction "A3_7") (pintype "input"))
      (node (ref "IC21") (pin "7") (pinfunction "A3_7") (pintype "input"))
      (node (ref "IC27") (pin "7") (pinfunction "A3_7") (pintype "input"))
      (node (ref "IC28") (pin "7") (pinfunction "A3_7") (pintype "input"))
      (node (ref "IC6") (pin "9") (pinfunction "4Q_9") (pintype "tri_state"))
    )
    (net (code "52") (name "MA9") (class "Default")
      (node (ref "IC20") (pin "8") (pinfunction "A2_8") (pintype "input"))
      (node (ref "IC21") (pin "8") (pinfunction "A2_8") (pintype "input"))
      (node (ref "IC27") (pin "8") (pinfunction "A2_8") (pintype "input"))
      (node (ref "IC28") (pin "8") (pinfunction "A2_8") (pintype "input"))
      (node (ref "IC6") (pin "6") (pinfunction "3Q_6") (pintype "tri_state"))
    )
    (net (code "53") (name "MA10") (class "Default")
      (node (ref "IC20") (pin "9") (pinfunction "A1_9") (pintype "input"))
      (node (ref "IC21") (pin "9") (pinfunction "A1_9") (pintype "input"))
      (node (ref "IC27") (pin "9") (pinfunction "A1_9") (pintype "input"))
      (node (ref "IC28") (pin "9") (pinfunction "A1_9") (pintype "input"))
      (node (ref "IC6") (pin "5") (pinfunction "2Q_5") (pintype "tri_state"))
    )
    (net (code "54") (name "MA11") (class "Default")
      (node (ref "IC20") (pin "10") (pinfunction "A0_10") (pintype "input"))
      (node (ref "IC21") (pin "10") (pinfunction "A0_10") (pintype "input"))
      (node (ref "IC27") (pin "10") (pinfunction "A0_10") (pintype "input"))
      (node (ref "IC28") (pin "10") (pinfunction "A0_10") (pintype "input"))
      (node (ref "IC6") (pin "2") (pinfunction "1Q_2") (pintype "tri_state"))
    )
    (net (code "55") (name "MEMSEL") (class "Default")
      (node (ref "IC10") (pin "5") (pinfunction "I1_5") (pintype "input"))
      (node (ref "IC25") (pin "4") (pinfunction "O_4") (pintype "output"))
      (node (ref "IC29") (pin "1") (pinfunction "I0_1") (pintype "input"))
      (node (ref "IC29") (pin "4") (pinfunction "I0_4") (pintype "input"))
    )
    (net (code "56") (name "Net-(CPUA-OSCOUT)") (class "Default")
      (node (ref "CPU") (pin "14") (pinfunction "OSCOUT_14") (pintype "output"))
      (node (ref "QG1") (pin "5") (pinfunction "OUT_5") (pintype "output"))
      (node (ref "QG2") (pin "8") (pinfunction "OUT_8") (pintype "output"))
    )
    (net (code "57") (name "Net-(IC11B-CLK)") (class "Default")
      (node (ref "IC11") (pin "11") (pinfunction "CLK_11") (pintype "input"))
      (node (ref "IC25") (pin "13") (pinfunction "O_13") (pintype "output"))
    )
    (net (code "58") (name "Net-(IC13D-I)") (class "Default")
      (node (ref "IC13") (pin "9") (pinfunction "I_9") (pintype "input"))
      (node (ref "IC8") (pin "6") (pinfunction "O_6") (pintype "output"))
    )
    (net (code "59") (name "Net-(IC13E-I)") (class "Default")
      (node (ref "IC13") (pin "11") (pinfunction "I_11") (pintype "input"))
      (node (ref "IC22") (pin "6") (pinfunction "O_6") (pintype "output"))
    )
    (net (code "60") (name "Net-(IC13F-I)") (class "Default")
      (node (ref "IC13") (pin "13") (pinfunction "I_13") (pintype "input"))
      (node (ref "IC19") (pin "3") (pinfunction "O_3") (pintype "output"))
    )
    (net (code "61") (name "Net-(IC15B-O)") (class "Default")
      (node (ref "IC1") (pin "13") (pinfunction "C12_13") (pintype "input"))
      (node (ref "IC1") (pin "4") (pinfunction "C34_4") (pintype "input"))
      (node (ref "IC15") (pin "6") (pinfunction "O_6") (pintype "output"))
      (node (ref "IC2") (pin "13") (pinfunction "C12_13") (pintype "input"))
      (node (ref "IC2") (pin "4") (pinfunction "C34_4") (pintype "input"))
      (node (ref "IC3") (pin "13") (pinfunction "C12_13") (pintype "input"))
      (node (ref "IC3") (pin "4") (pinfunction "C34_4") (pintype "input"))
    )
    (net (code "62") (name "Net-(IC16B-O)") (class "Default")
      (node (ref "IC16") (pin "6") (pinfunction "O_6") (pintype "output"))
      (node (ref "IC19") (pin "5") (pinfunction "I1_5") (pintype "input"))
    )
    (net (code "63") (name "Net-(IC17A-G)") (class "Default")
      (node (ref "IC17") (pin "1") (pinfunction "G_1") (pintype "input"))
      (node (ref "IC19") (pin "6") (pinfunction "O_6") (pintype "output"))
    )
    (net (code "64") (name "Net-(IC27A-~{CE})") (class "Default")
      (node (ref "IC27") (pin "20") (pinfunction "~{CE}_20") (pintype "input"))
      (node (ref "IC28") (pin "20") (pinfunction "~{CE}_20") (pintype "input"))
      (node (ref "IC29") (pin "8") (pinfunction "O_8") (pintype "output"))
    )
    (net (code "65") (name "Net-(IC27A-~{OE})") (class "Default")
      (node (ref "IC27") (pin "22") (pinfunction "~{OE}_22") (pintype "input"))
      (node (ref "IC28") (pin "22") (pinfunction "~{OE}_22") (pintype "input"))
      (node (ref "IC29") (pin "11") (pinfunction "O_11") (pintype "output"))
    )
    (net (code "66") (name "Net-(QG1-TS)") (class "Default")
      (node (ref "QG1") (pin "1") (pinfunction "TS_1") (pintype "passive"))
      (node (ref "QG2") (pin "1") (pinfunction "TS_1") (pintype "passive"))
    )
    (net (code "67") (name "POPR") (class "Default")
      (node (ref "IC10") (pin "2") (pinfunction "I1_2") (pintype "input"))
      (node (ref "IC14") (pin "12") (pinfunction "O_12") (pintype "output"))
    )
    (net (code "68") (name "RUN") (class "Default")
      (node (ref "CPU") (pin "2") (pinfunction "RUN_2") (pintype "output"))
      (node (ref "IC14") (pin "1") (pinfunction "I0_1") (pintype "input"))
      (node (ref "IC18") (pin "12") (pinfunction "I0_12") (pintype "input"))
    )
    (net (code "69") (name "SETIF") (class "Default")
      (node (ref "IC24") (pin "11") (pinfunction "CLK_11") (pintype "input"))
      (node (ref "IC26") (pin "5") (pinfunction "Q_5") (pintype "output"))
    )
    (net (code "70") (name "SETST") (class "Default")
      (node (ref "IC18") (pin "3") (pinfunction "O_3") (pintype "output"))
      (node (ref "IC4") (pin "11") (pinfunction "CLK_11") (pintype "input"))
      (node (ref "IC5") (pin "11") (pinfunction "CLK_11") (pintype "input"))
    )
    (net (code "71") (name "UB") (class "Default")
      (node (ref "IC24") (pin "8") (pinfunction "D4_8") (pintype "input"))
      (node (ref "IC4") (pin "16") (pinfunction "Q7_16") (pintype "output"))
    )
    (net (code "72") (name "UIF") (class "Default")
      (node (ref "IC22") (pin "5") (pinfunction "I_5") (pintype "input"))
      (node (ref "IC5") (pin "2") (pinfunction "Q1_2") (pintype "output"))
    )
    (net (code "73") (name "USEBF") (class "Default")
      (node (ref "IC19") (pin "4") (pinfunction "I0_4") (pintype "input"))
      (node (ref "IC22") (pin "10") (pinfunction "O_10") (pintype "output"))
    )
    (net (code "74") (name "USER_MODE") (class "Default")
      (node (ref "IC10") (pin "1") (pinfunction "I0_1") (pintype "input"))
      (node (ref "IC18") (pin "5") (pinfunction "I1_5") (pintype "input"))
      (node (ref "IC18") (pin "9") (pinfunction "I0_9") (pintype "input"))
      (node (ref "IC22") (pin "13") (pinfunction "I_13") (pintype "input"))
      (node (ref "IC24") (pin "9") (pinfunction "Q4_9") (pintype "output"))
    )
    (net (code "75") (name "VCC") (class "Default")
      (node (ref "IC11") (pin "10") (pinfunction "PRE_10") (pintype "input"))
      (node (ref "IC11") (pin "12") (pinfunction "D_12") (pintype "input"))
      (node (ref "IC11") (pin "2") (pinfunction "D_2") (pintype "input"))
      (node (ref "IC11") (pin "3") (pinfunction "CLK_3") (pintype "input"))
      (node (ref "IC12") (pin "1") (pinfunction "I0_1") (pintype "input"))
      (node (ref "IC12") (pin "2") (pinfunction "I1_2") (pintype "input"))
      (node (ref "IC15") (pin "10") (pinfunction "I1_10") (pintype "input"))
      (node (ref "IC15") (pin "12") (pinfunction "I0_12") (pintype "input"))
      (node (ref "IC15") (pin "13") (pinfunction "I1_13") (pintype "input"))
      (node (ref "IC15") (pin "9") (pinfunction "I0_9") (pintype "input"))
      (node (ref "IC19") (pin "12") (pinfunction "I0_12") (pintype "input"))
      (node (ref "IC19") (pin "13") (pinfunction "I1_13") (pintype "input"))
      (node (ref "IC20") (pin "28") (pinfunction "VCC_28") (pintype "power_in"))
      (node (ref "IC21") (pin "28") (pinfunction "VCC_28") (pintype "power_in"))
      (node (ref "IC24") (pin "13") (pinfunction "D5_13") (pintype "input"))
      (node (ref "IC24") (pin "14") (pinfunction "D6_14") (pintype "input"))
      (node (ref "IC24") (pin "17") (pinfunction "D7_17") (pintype "input"))
      (node (ref "IC24") (pin "18") (pinfunction "D8_18") (pintype "input"))
      (node (ref "IC25") (pin "8") (pinfunction "I0_8") (pintype "input"))
      (node (ref "IC25") (pin "9") (pinfunction "I1_9") (pintype "input"))
      (node (ref "IC26") (pin "1") (pinfunction "CLR_1") (pintype "input"))
      (node (ref "IC26") (pin "10") (pinfunction "PRE_10") (pintype "input"))
      (node (ref "IC26") (pin "11") (pinfunction "CLK_11") (pintype "input"))
      (node (ref "IC26") (pin "12") (pinfunction "D_12") (pintype "input"))
      (node (ref "IC26") (pin "13") (pinfunction "CLR_13") (pintype "input"))
      (node (ref "IC26") (pin "4") (pinfunction "PRE_4") (pintype "input"))
      (node (ref "IC5") (pin "13") (pinfunction "D5_13") (pintype "input"))
      (node (ref "IC5") (pin "14") (pinfunction "D6_14") (pintype "input"))
      (node (ref "IC5") (pin "17") (pinfunction "D7_17") (pintype "input"))
      (node (ref "IC5") (pin "18") (pinfunction "D8_18") (pintype "input"))
      (node (ref "IC9") (pin "6") (pinfunction "G1_6") (pintype "input"))
      (node (ref "QG1") (pin "8") (pinfunction "VCC_8") (pintype "power_in"))
      (node (ref "QG2") (pin "14") (pinfunction "VCC_14") (pintype "power_in"))
      (node (ref "RN1") (pin "1") (pinfunction "1_1") (pintype "passive"))
      (node (ref "SV1") (pin "1") (pinfunction "1_1") (pintype "passive"))
      (node (ref "SV1") (pin "40") (pinfunction "40_40") (pintype "passive"))
    )
    (net (code "76") (name "WASMEM") (class "Default")
      (node (ref "IC11") (pin "9") (pinfunction "Q_9") (pintype "output"))
      (node (ref "IC14") (pin "9") (pinfunction "I0_9") (pintype "input"))
      (node (ref "IC8") (pin "5") (pinfunction "I2_5") (pintype "input"))
    )
    (net (code "77") (name "XTA") (class "Default")
      (node (ref "CPU") (pin "9") (pinfunction "XTA_9") (pintype "output"))
      (node (ref "IC15") (pin "5") (pinfunction "I1_5") (pintype "input"))
      (node (ref "IC22") (pin "1") (pinfunction "I_1") (pintype "input"))
      (node (ref "IC29") (pin "13") (pinfunction "I1_13") (pintype "input"))
      (node (ref "IC29") (pin "5") (pinfunction "I1_5") (pintype "input"))
      (node (ref "SV1") (pin "10") (pinfunction "10_10") (pintype "passive"))
    )
    (net (code "78") (name "XTB") (class "Default")
      (node (ref "CPU") (pin "12") (pinfunction "XTB_12") (pintype "output"))
      (node (ref "IC22") (pin "3") (pinfunction "I_3") (pintype "input"))
      (node (ref "IC29") (pin "2") (pinfunction "I1_2") (pintype "input"))
      (node (ref "SV1") (pin "12") (pinfunction "12_12") (pintype "passive"))
    )
    (net (code "79") (name "XTC") (class "Default")
      (node (ref "CPU") (pin "13") (pinfunction "XTC_13") (pintype "output"))
      (node (ref "IC19") (pin "10") (pinfunction "I1_10") (pintype "input"))
      (node (ref "SV1") (pin "14") (pinfunction "14_14") (pintype "passive"))
    )
    (net (code "80") (name "ZF") (class "Default")
      (node (ref "IC11") (pin "5") (pinfunction "Q_5") (pintype "output"))
      (node (ref "IC16") (pin "5") (pinfunction "I1_5") (pintype "input"))
    )
    (net (code "81") (name "unconnected-(IC1A-Q4-Pad9)") (class "Default")
      (node (ref "IC1") (pin "9") (pinfunction "Q4_9") (pintype "output"))
    )
    (net (code "82") (name "unconnected-(IC1A-~{Q1}-Pad1)") (class "Default")
      (node (ref "IC1") (pin "1") (pinfunction "~{Q1}_1") (pintype "output"))
    )
    (net (code "83") (name "unconnected-(IC1A-~{Q2}-Pad14)") (class "Default")
      (node (ref "IC1") (pin "14") (pinfunction "~{Q2}_14") (pintype "output"))
    )
    (net (code "84") (name "unconnected-(IC1A-~{Q3}-Pad11)") (class "Default")
      (node (ref "IC1") (pin "11") (pinfunction "~{Q3}_11") (pintype "output"))
    )
    (net (code "85") (name "unconnected-(IC2A-Q2-Pad15)") (class "Default")
      (node (ref "IC2") (pin "15") (pinfunction "Q2_15") (pintype "output"))
    )
    (net (code "86") (name "unconnected-(IC2A-Q3-Pad10)") (class "Default")
      (node (ref "IC2") (pin "10") (pinfunction "Q3_10") (pintype "output"))
    )
    (net (code "87") (name "unconnected-(IC2A-Q4-Pad9)") (class "Default")
      (node (ref "IC2") (pin "9") (pinfunction "Q4_9") (pintype "output"))
    )
    (net (code "88") (name "unconnected-(IC3A-Q1-Pad16)") (class "Default")
      (node (ref "IC3") (pin "16") (pinfunction "Q1_16") (pintype "output"))
    )
    (net (code "89") (name "unconnected-(IC3A-~{Q2}-Pad14)") (class "Default")
      (node (ref "IC3") (pin "14") (pinfunction "~{Q2}_14") (pintype "output"))
    )
    (net (code "90") (name "unconnected-(IC3A-~{Q3}-Pad11)") (class "Default")
      (node (ref "IC3") (pin "11") (pinfunction "~{Q3}_11") (pintype "output"))
    )
    (net (code "91") (name "unconnected-(IC3A-~{Q4}-Pad8)") (class "Default")
      (node (ref "IC3") (pin "8") (pinfunction "~{Q4}_8") (pintype "output"))
    )
    (net (code "92") (name "unconnected-(IC5A-Q2-Pad5)") (class "Default")
      (node (ref "IC5") (pin "5") (pinfunction "Q2_5") (pintype "output"))
    )
    (net (code "93") (name "unconnected-(IC5A-Q3-Pad6)") (class "Default")
      (node (ref "IC5") (pin "6") (pinfunction "Q3_6") (pintype "output"))
    )
    (net (code "94") (name "unconnected-(IC5A-Q4-Pad9)") (class "Default")
      (node (ref "IC5") (pin "9") (pinfunction "Q4_9") (pintype "output"))
    )
    (net (code "95") (name "unconnected-(IC5A-Q5-Pad12)") (class "Default")
      (node (ref "IC5") (pin "12") (pinfunction "Q5_12") (pintype "output"))
    )
    (net (code "96") (name "unconnected-(IC5A-Q6-Pad15)") (class "Default")
      (node (ref "IC5") (pin "15") (pinfunction "Q6_15") (pintype "output"))
    )
    (net (code "97") (name "unconnected-(IC5A-Q7-Pad16)") (class "Default")
      (node (ref "IC5") (pin "16") (pinfunction "Q7_16") (pintype "output"))
    )
    (net (code "98") (name "unconnected-(IC5A-Q8-Pad19)") (class "Default")
      (node (ref "IC5") (pin "19") (pinfunction "Q8_19") (pintype "output"))
    )
    (net (code "99") (name "unconnected-(IC7A-5Q-Pad12)") (class "Default")
      (node (ref "IC7") (pin "12") (pinfunction "5Q_12") (pintype "tri_state"))
    )
    (net (code "100") (name "unconnected-(IC7A-6Q-Pad15)") (class "Default")
      (node (ref "IC7") (pin "15") (pinfunction "6Q_15") (pintype "tri_state"))
    )
    (net (code "101") (name "unconnected-(IC7A-7Q-Pad16)") (class "Default")
      (node (ref "IC7") (pin "16") (pinfunction "7Q_16") (pintype "tri_state"))
    )
    (net (code "102") (name "unconnected-(IC7A-8Q-Pad19)") (class "Default")
      (node (ref "IC7") (pin "19") (pinfunction "8Q_19") (pintype "tri_state"))
    )
    (net (code "103") (name "unconnected-(IC11A-~{Q}-Pad6)") (class "Default")
      (node (ref "IC11") (pin "6") (pinfunction "~{Q}_6") (pintype "output"))
    )
    (net (code "104") (name "unconnected-(IC11B-~{Q}-Pad8)") (class "Default")
      (node (ref "IC11") (pin "8") (pinfunction "~{Q}_8") (pintype "output"))
    )
    (net (code "105") (name "unconnected-(IC15C-O-Pad8)") (class "Default")
      (node (ref "IC15") (pin "8") (pinfunction "O_8") (pintype "output"))
    )
    (net (code "106") (name "unconnected-(IC15D-O-Pad11)") (class "Default")
      (node (ref "IC15") (pin "11") (pinfunction "O_11") (pintype "output"))
    )
    (net (code "107") (name "unconnected-(IC17A-Y4-Pad12)") (class "Default")
      (node (ref "IC17") (pin "12") (pinfunction "Y4_12") (pintype "tri_state"))
    )
    (net (code "108") (name "unconnected-(IC17B-Y4-Pad3)") (class "Default")
      (node (ref "IC17") (pin "3") (pinfunction "Y4_3") (pintype "tri_state"))
    )
    (net (code "109") (name "unconnected-(IC19D-O-Pad11)") (class "Default")
      (node (ref "IC19") (pin "11") (pinfunction "O_11") (pintype "output"))
    )
    (net (code "110") (name "unconnected-(IC21-I{slash}O4-Pad16)") (class "Default")
      (node (ref "IC21") (pin "16") (pinfunction "I/O4_16") (pintype "bidirectional"))
    )
    (net (code "111") (name "unconnected-(IC21-I{slash}O5-Pad17)") (class "Default")
      (node (ref "IC21") (pin "17") (pinfunction "I/O5_17") (pintype "bidirectional"))
    )
    (net (code "112") (name "unconnected-(IC21-I{slash}O6-Pad18)") (class "Default")
      (node (ref "IC21") (pin "18") (pinfunction "I/O6_18") (pintype "bidirectional"))
    )
    (net (code "113") (name "unconnected-(IC21-I{slash}O7-Pad19)") (class "Default")
      (node (ref "IC21") (pin "19") (pinfunction "I/O7_19") (pintype "bidirectional"))
    )
    (net (code "114") (name "unconnected-(IC23A-Y4-Pad12)") (class "Default")
      (node (ref "IC23") (pin "12") (pinfunction "Y4_12") (pintype "tri_state"))
    )
    (net (code "115") (name "unconnected-(IC23B-Y1-Pad9)") (class "Default")
      (node (ref "IC23") (pin "9") (pinfunction "Y1_9") (pintype "tri_state"))
    )
    (net (code "116") (name "unconnected-(IC23B-Y2-Pad7)") (class "Default")
      (node (ref "IC23") (pin "7") (pinfunction "Y2_7") (pintype "tri_state"))
    )
    (net (code "117") (name "unconnected-(IC23B-Y3-Pad5)") (class "Default")
      (node (ref "IC23") (pin "5") (pinfunction "Y3_5") (pintype "tri_state"))
    )
    (net (code "118") (name "unconnected-(IC23B-Y4-Pad3)") (class "Default")
      (node (ref "IC23") (pin "3") (pinfunction "Y4_3") (pintype "tri_state"))
    )
    (net (code "119") (name "unconnected-(IC24A-Q5-Pad12)") (class "Default")
      (node (ref "IC24") (pin "12") (pinfunction "Q5_12") (pintype "output"))
    )
    (net (code "120") (name "unconnected-(IC24A-Q6-Pad15)") (class "Default")
      (node (ref "IC24") (pin "15") (pinfunction "Q6_15") (pintype "output"))
    )
    (net (code "121") (name "unconnected-(IC24A-Q7-Pad16)") (class "Default")
      (node (ref "IC24") (pin "16") (pinfunction "Q7_16") (pintype "output"))
    )
    (net (code "122") (name "unconnected-(IC24A-Q8-Pad19)") (class "Default")
      (node (ref "IC24") (pin "19") (pinfunction "Q8_19") (pintype "output"))
    )
    (net (code "123") (name "unconnected-(IC25C-O-Pad10)") (class "Default")
      (node (ref "IC25") (pin "10") (pinfunction "O_10") (pintype "output"))
    )
    (net (code "124") (name "unconnected-(IC26A-~{Q}-Pad6)") (class "Default")
      (node (ref "IC26") (pin "6") (pinfunction "~{Q}_6") (pintype "output"))
    )
    (net (code "125") (name "unconnected-(IC26B-Q-Pad9)") (class "Default")
      (node (ref "IC26") (pin "9") (pinfunction "Q_9") (pintype "output"))
    )
    (net (code "126") (name "unconnected-(IC26B-~{Q}-Pad8)") (class "Default")
      (node (ref "IC26") (pin "8") (pinfunction "~{Q}_8") (pintype "output"))
    )
    (net (code "127") (name "unconnected-(IC28A-O4-Pad16)") (class "Default")
      (node (ref "IC28") (pin "16") (pinfunction "O4_16") (pintype "tri_state"))
    )
    (net (code "128") (name "unconnected-(IC28A-O5-Pad17)") (class "Default")
      (node (ref "IC28") (pin "17") (pinfunction "O5_17") (pintype "tri_state"))
    )
    (net (code "129") (name "unconnected-(IC28A-O6-Pad18)") (class "Default")
      (node (ref "IC28") (pin "18") (pinfunction "O6_18") (pintype "tri_state"))
    )
    (net (code "130") (name "unconnected-(IC28A-O7-Pad19)") (class "Default")
      (node (ref "IC28") (pin "19") (pinfunction "O7_19") (pintype "tri_state"))
    )
    (net (code "131") (name "unconnected-(RN1-Pad12)") (class "Default")
      (node (ref "RN1") (pin "12") (pinfunction "12_12") (pintype "passive"))
    )
    (net (code "132") (name "unconnected-(RN1-Pad13)") (class "Default")
      (node (ref "RN1") (pin "13") (pinfunction "13_13") (pintype "passive"))
    )
    (net (code "133") (name "unconnected-(SPARE1-Pad1)") (class "Default")
      (node (ref "SPARE1") (pin "1") (pinfunction "1_1") (pintype "passive"))
    )
    (net (code "134") (name "unconnected-(SPARE1-Pad2)") (class "Default")
      (node (ref "SPARE1") (pin "2") (pinfunction "2_2") (pintype "passive"))
    )
    (net (code "135") (name "unconnected-(SPARE1-Pad3)") (class "Default")
      (node (ref "SPARE1") (pin "3") (pinfunction "3_3") (pintype "passive"))
    )
    (net (code "136") (name "unconnected-(SPARE1-Pad4)") (class "Default")
      (node (ref "SPARE1") (pin "4") (pinfunction "4_4") (pintype "passive"))
    )
    (net (code "137") (name "unconnected-(SPARE1-Pad5)") (class "Default")
      (node (ref "SPARE1") (pin "5") (pinfunction "5_5") (pintype "passive"))
    )
    (net (code "138") (name "unconnected-(SPARE1-Pad6)") (class "Default")
      (node (ref "SPARE1") (pin "6") (pinfunction "6_6") (pintype "passive"))
    )
    (net (code "139") (name "unconnected-(SPARE1-Pad7)") (class "Default")
      (node (ref "SPARE1") (pin "7") (pinfunction "7_7") (pintype "passive"))
    )
    (net (code "140") (name "unconnected-(SPARE1-Pad8)") (class "Default")
      (node (ref "SPARE1") (pin "8") (pinfunction "8_8") (pintype "passive"))
    )
    (net (code "141") (name "unconnected-(SPARE1-Pad9)") (class "Default")
      (node (ref "SPARE1") (pin "9") (pinfunction "9_9") (pintype "passive"))
    )
    (net (code "142") (name "unconnected-(SPARE1-Pad10)") (class "Default")
      (node (ref "SPARE1") (pin "10") (pinfunction "10_10") (pintype "passive"))
    )
    (net (code "143") (name "unconnected-(SPARE1-Pad11)") (class "Default")
      (node (ref "SPARE1") (pin "11") (pinfunction "11_11") (pintype "passive"))
    )
    (net (code "144") (name "unconnected-(SPARE1-Pad12)") (class "Default")
      (node (ref "SPARE1") (pin "12") (pinfunction "12_12") (pintype "passive"))
    )
    (net (code "145") (name "unconnected-(SPARE1-Pad13)") (class "Default")
      (node (ref "SPARE1") (pin "13") (pinfunction "13_13") (pintype "passive"))
    )
    (net (code "146") (name "unconnected-(SPARE1-Pad14)") (class "Default")
      (node (ref "SPARE1") (pin "14") (pinfunction "14_14") (pintype "passive"))
    )
    (net (code "147") (name "unconnected-(SPARE1-Pad15)") (class "Default")
      (node (ref "SPARE1") (pin "15") (pinfunction "15_15") (pintype "passive"))
    )
    (net (code "148") (name "unconnected-(SPARE1-Pad16)") (class "Default")
      (node (ref "SPARE1") (pin "16") (pinfunction "16_16") (pintype "passive"))
    )
    (net (code "149") (name "unconnected-(SPARE1-Pad17)") (class "Default")
      (node (ref "SPARE1") (pin "17") (pinfunction "17_17") (pintype "passive"))
    )
    (net (code "150") (name "unconnected-(SPARE1-Pad18)") (class "Default")
      (node (ref "SPARE1") (pin "18") (pinfunction "18_18") (pintype "passive"))
    )
    (net (code "151") (name "unconnected-(SPARE1-Pad19)") (class "Default")
      (node (ref "SPARE1") (pin "19") (pinfunction "19_19") (pintype "passive"))
    )
    (net (code "152") (name "unconnected-(SPARE1-Pad20)") (class "Default")
      (node (ref "SPARE1") (pin "20") (pinfunction "20_20") (pintype "passive"))
    )
    (net (code "153") (name "unconnected-(SV1-Pad3)") (class "Default")
      (node (ref "SV1") (pin "3") (pinfunction "3_3") (pintype "passive"))
    )
    (net (code "154") (name "unconnected-(SV1-Pad4)") (class "Default")
      (node (ref "SV1") (pin "4") (pinfunction "4_4") (pintype "passive"))
    )
    (net (code "155") (name "unconnected-(SV1-Pad37)") (class "Default")
      (node (ref "SV1") (pin "37") (pinfunction "37_37") (pintype "passive"))
    )
    (net (code "156") (name "~{00FLT}") (class "Default")
      (node (ref "IC13") (pin "3") (pinfunction "I_3") (pintype "input"))
      (node (ref "IC16") (pin "8") (pinfunction "O_8") (pintype "output"))
    )
    (net (code "157") (name "~{00}") (class "Default")
      (node (ref "IC12") (pin "8") (pinfunction "O_8") (pintype "output"))
      (node (ref "IC16") (pin "9") (pinfunction "I0_9") (pintype "input"))
    )
    (net (code "158") (name "~{2XFLT}") (class "Default")
      (node (ref "IC13") (pin "5") (pinfunction "I_5") (pintype "input"))
      (node (ref "IC16") (pin "11") (pinfunction "O_11") (pintype "output"))
      (node (ref "IC18") (pin "2") (pinfunction "I1_2") (pintype "input"))
    )
    (net (code "159") (name "~{2X}") (class "Default")
      (node (ref "IC14") (pin "6") (pinfunction "O_6") (pintype "output"))
      (node (ref "IC16") (pin "12") (pinfunction "I0_12") (pintype "input"))
    )
    (net (code "160") (name "~{AND}") (class "Default")
      (node (ref "IC9") (pin "15") (pinfunction "Y0_15") (pintype "output"))
      (node (ref "PAD1") (pin "1") (pinfunction "P_1") (pintype "passive"))
    )
    (net (code "161") (name "~{BADHLT}") (class "Default")
      (node (ref "IC18") (pin "11") (pinfunction "O_11") (pintype "output"))
      (node (ref "IC19") (pin "1") (pinfunction "I0_1") (pintype "input"))
    )
    (net (code "162") (name "~{C0}") (class "Default")
      (node (ref "CPU") (pin "32") (pinfunction "C0_32") (pintype "input"))
      (node (ref "RN1") (pin "8") (pinfunction "8_8") (pintype "passive"))
      (node (ref "SV1") (pin "24") (pinfunction "24_24") (pintype "passive"))
    )
    (net (code "163") (name "~{C1}") (class "Default")
      (node (ref "CPU") (pin "33") (pinfunction "C1_33") (pintype "input"))
      (node (ref "RN1") (pin "9") (pinfunction "9_9") (pintype "passive"))
      (node (ref "SV1") (pin "22") (pinfunction "22_22") (pintype "passive"))
    )
    (net (code "164") (name "~{C2}") (class "Default")
      (node (ref "CPU") (pin "34") (pinfunction "C2_34") (pintype "input"))
      (node (ref "RN1") (pin "10") (pinfunction "10_10") (pintype "passive"))
      (node (ref "SV1") (pin "20") (pinfunction "20_20") (pintype "passive"))
    )
    (net (code "165") (name "~{CLRST}") (class "Default")
      (node (ref "IC15") (pin "3") (pinfunction "O_3") (pintype "output"))
      (node (ref "IC24") (pin "1") (pinfunction "CLR_1") (pintype "input"))
      (node (ref "IC4") (pin "1") (pinfunction "CLR_1") (pintype "input"))
      (node (ref "IC5") (pin "1") (pinfunction "CLR_1") (pintype "input"))
    )
    (net (code "166") (name "~{CPREQ}") (class "Default")
      (node (ref "CPU") (pin "5") (pinfunction "CPREQ_5") (pintype "input"))
      (node (ref "IC13") (pin "2") (pinfunction "O_2") (pintype "open_collector"))
      (node (ref "IC13") (pin "4") (pinfunction "O_4") (pintype "open_collector"))
      (node (ref "IC13") (pin "6") (pinfunction "O_6") (pintype "open_collector"))
      (node (ref "IC13") (pin "8") (pinfunction "O_8") (pintype "open_collector"))
      (node (ref "RN1") (pin "6") (pinfunction "6_6") (pintype "passive"))
      (node (ref "SV1") (pin "36") (pinfunction "36_36") (pintype "passive"))
    )
    (net (code "167") (name "~{CPSEL}") (class "Default")
      (node (ref "CPU") (pin "38") (pinfunction "CPSEL_38") (pintype "output"))
      (node (ref "IC22") (pin "9") (pinfunction "I_9") (pintype "input"))
    )
    (net (code "168") (name "~{CPUDEVSEL}") (class "Default")
      (node (ref "CPU") (pin "30") (pinfunction "DEVSEL_30") (pintype "output"))
      (node (ref "IC11") (pin "1") (pinfunction "CLR_1") (pintype "input"))
      (node (ref "IC14") (pin "13") (pinfunction "I2_13") (pintype "input"))
      (node (ref "IC16") (pin "10") (pinfunction "I1_10") (pintype "input"))
      (node (ref "IC16") (pin "13") (pinfunction "I1_13") (pintype "input"))
      (node (ref "IC18") (pin "4") (pinfunction "I0_4") (pintype "input"))
    )
    (net (code "169") (name "~{CPUINTREQ}") (class "Default")
      (node (ref "CPU") (pin "8") (pinfunction "INTREQ_8") (pintype "input"))
      (node (ref "IC16") (pin "3") (pinfunction "O_3") (pintype "output"))
      (node (ref "RN1") (pin "3") (pinfunction "3_3") (pintype "passive"))
    )
    (net (code "170") (name "~{CPUSWSEL}") (class "Default")
      (node (ref "CPU") (pin "31") (pinfunction "SWSEL_31") (pintype "output"))
      (node (ref "IC14") (pin "2") (pinfunction "I1_2") (pintype "input"))
      (node (ref "IC18") (pin "10") (pinfunction "I1_10") (pintype "input"))
    )
    (net (code "171") (name "~{DCA}") (class "Default")
      (node (ref "IC9") (pin "12") (pinfunction "Y3_12") (pintype "output"))
      (node (ref "PAD4") (pin "1") (pinfunction "P_1") (pintype "passive"))
    )
    (net (code "172") (name "~{DEVSEL}") (class "Default")
      (node (ref "IC18") (pin "6") (pinfunction "O_6") (pintype "output"))
      (node (ref "SV1") (pin "16") (pinfunction "16_16") (pintype "passive"))
    )
    (net (code "173") (name "~{DMAREQ}") (class "Default")
      (node (ref "CPU") (pin "4") (pinfunction "DMAREQ_4") (pintype "input"))
      (node (ref "RN1") (pin "7") (pinfunction "7_7") (pintype "passive"))
      (node (ref "SV1") (pin "7") (pinfunction "7_7") (pintype "passive"))
    )
    (net (code "174") (name "~{ERROR}") (class "Default")
      (node (ref "IC10") (pin "3") (pinfunction "O_3") (pintype "output"))
      (node (ref "IC13") (pin "1") (pinfunction "I_1") (pintype "input"))
    )
    (net (code "175") (name "~{INTCLR}") (class "Default")
      (node (ref "IC10") (pin "11") (pinfunction "O_11") (pintype "output"))
      (node (ref "IC15") (pin "2") (pinfunction "I1_2") (pintype "input"))
    )
    (net (code "176") (name "~{INTREQ}") (class "Default")
      (node (ref "IC13") (pin "10") (pinfunction "O_10") (pintype "open_collector"))
      (node (ref "IC16") (pin "1") (pinfunction "I0_1") (pintype "input"))
      (node (ref "SV1") (pin "8") (pinfunction "8_8") (pintype "passive"))
    )
    (net (code "177") (name "~{IOT}") (class "Default")
      (node (ref "IC9") (pin "9") (pinfunction "Y6_9") (pintype "output"))
      (node (ref "PAD7") (pin "1") (pinfunction "P_1") (pintype "passive"))
    )
    (net (code "178") (name "~{IR3}") (class "Default")
      (node (ref "IC12") (pin "12") (pinfunction "I7_12") (pintype "input"))
      (node (ref "IC14") (pin "5") (pinfunction "I2_5") (pintype "input"))
      (node (ref "IC3") (pin "1") (pinfunction "~{Q1}_1") (pintype "output"))
    )
    (net (code "179") (name "~{IR4}") (class "Default")
      (node (ref "IC12") (pin "11") (pinfunction "I6_11") (pintype "input"))
      (node (ref "IC2") (pin "1") (pinfunction "~{Q1}_1") (pintype "output"))
    )
    (net (code "180") (name "~{IR5}") (class "Default")
      (node (ref "IC12") (pin "6") (pinfunction "I5_6") (pintype "input"))
      (node (ref "IC14") (pin "3") (pinfunction "I0_3") (pintype "input"))
      (node (ref "IC2") (pin "14") (pinfunction "~{Q2}_14") (pintype "output"))
    )
    (net (code "181") (name "~{IR6}") (class "Default")
      (node (ref "IC12") (pin "5") (pinfunction "I4_5") (pintype "input"))
      (node (ref "IC2") (pin "11") (pinfunction "~{Q3}_11") (pintype "output"))
    )
    (net (code "182") (name "~{IR7}") (class "Default")
      (node (ref "IC12") (pin "4") (pinfunction "I3_4") (pintype "input"))
      (node (ref "IC2") (pin "8") (pinfunction "~{Q4}_8") (pintype "output"))
    )
    (net (code "183") (name "~{IR8}") (class "Default")
      (node (ref "IC1") (pin "8") (pinfunction "~{Q4}_8") (pintype "output"))
      (node (ref "IC12") (pin "3") (pinfunction "I2_3") (pintype "input"))
    )
    (net (code "184") (name "~{ISZ}") (class "Default")
      (node (ref "IC9") (pin "13") (pinfunction "Y2_13") (pintype "output"))
      (node (ref "PAD3") (pin "1") (pinfunction "P_1") (pintype "passive"))
    )
    (net (code "185") (name "~{JMP_OR_JMS}") (class "Default")
      (node (ref "IC19") (pin "9") (pinfunction "I0_9") (pintype "input"))
      (node (ref "IC25") (pin "1") (pinfunction "O_1") (pintype "output"))
    )
    (net (code "186") (name "~{JMP}") (class "Default")
      (node (ref "IC10") (pin "9") (pinfunction "I0_9") (pintype "input"))
      (node (ref "IC9") (pin "10") (pinfunction "Y5_10") (pintype "output"))
    )
    (net (code "187") (name "~{JMS}") (class "Default")
      (node (ref "IC10") (pin "10") (pinfunction "I1_10") (pintype "input"))
      (node (ref "IC9") (pin "11") (pinfunction "Y4_11") (pintype "output"))
    )
    (net (code "188") (name "~{MEMFETCH}") (class "Default")
      (node (ref "IC10") (pin "6") (pinfunction "O_6") (pintype "output"))
      (node (ref "IC25") (pin "11") (pinfunction "I0_11") (pintype "input"))
      (node (ref "IC25") (pin "12") (pinfunction "I1_12") (pintype "input"))
    )
    (net (code "189") (name "~{MEMSEL}") (class "Default")
      (node (ref "CPU") (pin "37") (pinfunction "MEMSEL_37") (pintype "output"))
      (node (ref "IC20") (pin "20") (pinfunction "~{CS}_20") (pintype "input"))
      (node (ref "IC21") (pin "20") (pinfunction "~{CS}_20") (pintype "input"))
      (node (ref "IC25") (pin "5") (pinfunction "I0_5") (pintype "input"))
      (node (ref "IC25") (pin "6") (pinfunction "I1_6") (pintype "input"))
    )
    (net (code "190") (name "~{OE}") (class "Default")
      (node (ref "IC20") (pin "22") (pinfunction "~{OE}_22") (pintype "input"))
      (node (ref "IC21") (pin "22") (pinfunction "~{OE}_22") (pintype "input"))
      (node (ref "IC29") (pin "6") (pinfunction "O_6") (pintype "output"))
    )
    (net (code "191") (name "~{OPR}") (class "Default")
      (node (ref "IC9") (pin "7") (pinfunction "Y7_7") (pintype "output"))
      (node (ref "PAD6") (pin "1") (pinfunction "P_1") (pintype "passive"))
    )
    (net (code "192") (name "~{RESET}") (class "Default")
      (node (ref "CPU") (pin "7") (pinfunction "RESET_7") (pintype "input"))
      (node (ref "IC15") (pin "1") (pinfunction "I0_1") (pintype "input"))
      (node (ref "RN1") (pin "4") (pinfunction "4_4") (pintype "passive"))
      (node (ref "SV1") (pin "11") (pinfunction "11_11") (pintype "passive"))
    )
    (net (code "193") (name "~{RUNHLT}") (class "Default")
      (node (ref "CPU") (pin "6") (pinfunction "RUNHLT_6") (pintype "input"))
      (node (ref "IC13") (pin "12") (pinfunction "O_12") (pintype "open_collector"))
      (node (ref "RN1") (pin "5") (pinfunction "5_5") (pintype "passive"))
      (node (ref "SV1") (pin "9") (pinfunction "9_9") (pintype "passive"))
    )
    (net (code "194") (name "~{SETZF}") (class "Default")
      (node (ref "IC11") (pin "13") (pinfunction "CLR_13") (pintype "input"))
      (node (ref "IC11") (pin "4") (pinfunction "PRE_4") (pintype "input"))
      (node (ref "IC14") (pin "8") (pinfunction "O_8") (pintype "output"))
      (node (ref "IC19") (pin "2") (pinfunction "I1_2") (pintype "input"))
    )
    (net (code "195") (name "~{SKP}") (class "Default")
      (node (ref "CPU") (pin "35") (pinfunction "SKP_35") (pintype "input"))
      (node (ref "RN1") (pin "11") (pinfunction "11_11") (pintype "passive"))
      (node (ref "SV1") (pin "18") (pinfunction "18_18") (pintype "passive"))
    )
    (net (code "196") (name "~{SWSEL}") (class "Default")
      (node (ref "IC18") (pin "8") (pinfunction "O_8") (pintype "output"))
      (node (ref "SV1") (pin "38") (pinfunction "38_38") (pintype "passive"))
    )
    (net (code "197") (name "~{TAD}") (class "Default")
      (node (ref "IC9") (pin "14") (pinfunction "Y1_14") (pintype "output"))
      (node (ref "PAD2") (pin "1") (pinfunction "P_1") (pintype "passive"))
    )
    (net (code "198") (name "~{USEBF}") (class "Default")
      (node (ref "IC19") (pin "8") (pinfunction "O_8") (pintype "output"))
      (node (ref "IC22") (pin "11") (pinfunction "I_11") (pintype "input"))
      (node (ref "IC23") (pin "1") (pinfunction "G_1") (pintype "input"))
    )
    (net (code "199") (name "~{USER_MODE}") (class "Default")
      (node (ref "IC18") (pin "13") (pinfunction "I1_13") (pintype "input"))
      (node (ref "IC22") (pin "12") (pinfunction "O_12") (pintype "output"))
    )
    (net (code "200") (name "~{WAIT}") (class "Default")
      (node (ref "CPU") (pin "11") (pinfunction "WAIT_11") (pintype "input"))
      (node (ref "RN1") (pin "2") (pinfunction "2_2") (pintype "passive"))
      (node (ref "SV1") (pin "26") (pinfunction "26_26") (pintype "passive"))
    )
    (net (code "201") (name "~{WE}") (class "Default")
      (node (ref "IC20") (pin "27") (pinfunction "~{WE}_27") (pintype "input"))
      (node (ref "IC21") (pin "27") (pinfunction "~{WE}_27") (pintype "input"))
      (node (ref "IC29") (pin "3") (pinfunction "O_3") (pintype "output"))
    )
    (net (code "202") (name "~{XTA}") (class "Default")
      (node (ref "IC22") (pin "2") (pinfunction "O_2") (pintype "output"))
    )
    (net (code "203") (name "~{XTB}") (class "Default")
      (node (ref "IC22") (pin "4") (pinfunction "O_4") (pintype "output"))
    )
    (net (code "204") (name "~{XXX7}") (class "Default")
      (node (ref "IC18") (pin "1") (pinfunction "I0_1") (pintype "input"))
      (node (ref "IC8") (pin "8") (pinfunction "O_8") (pintype "output"))
    )
  )
)
